# zx_kit_example.net
KiCad netlist of a schematic drawn in EAGLE
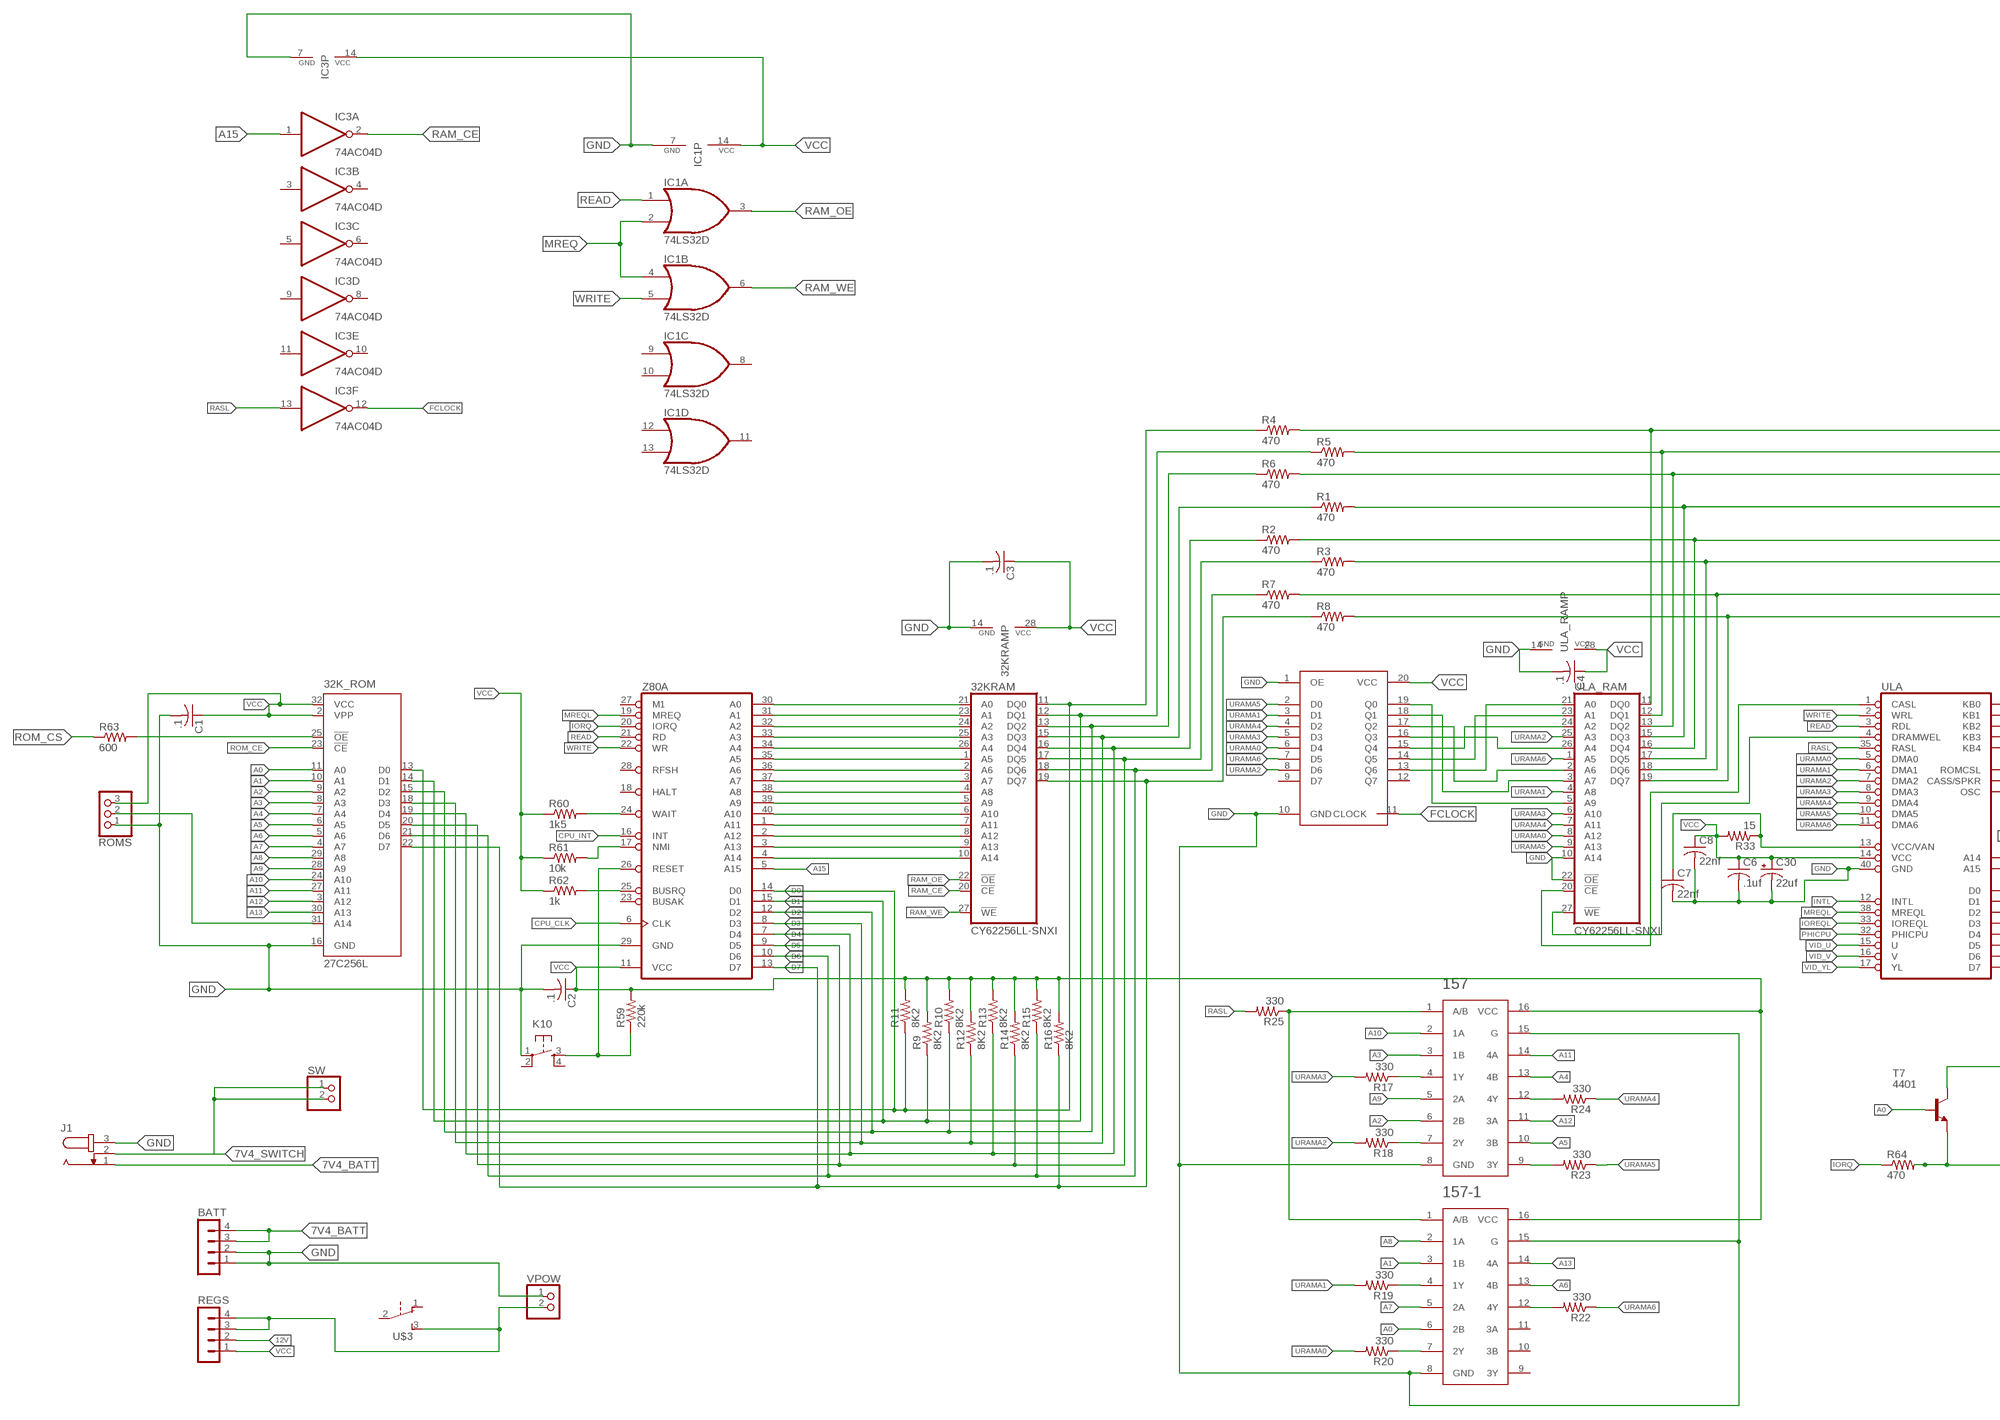
[diagram p0: schematic, sheet 1, part 1 of 3]
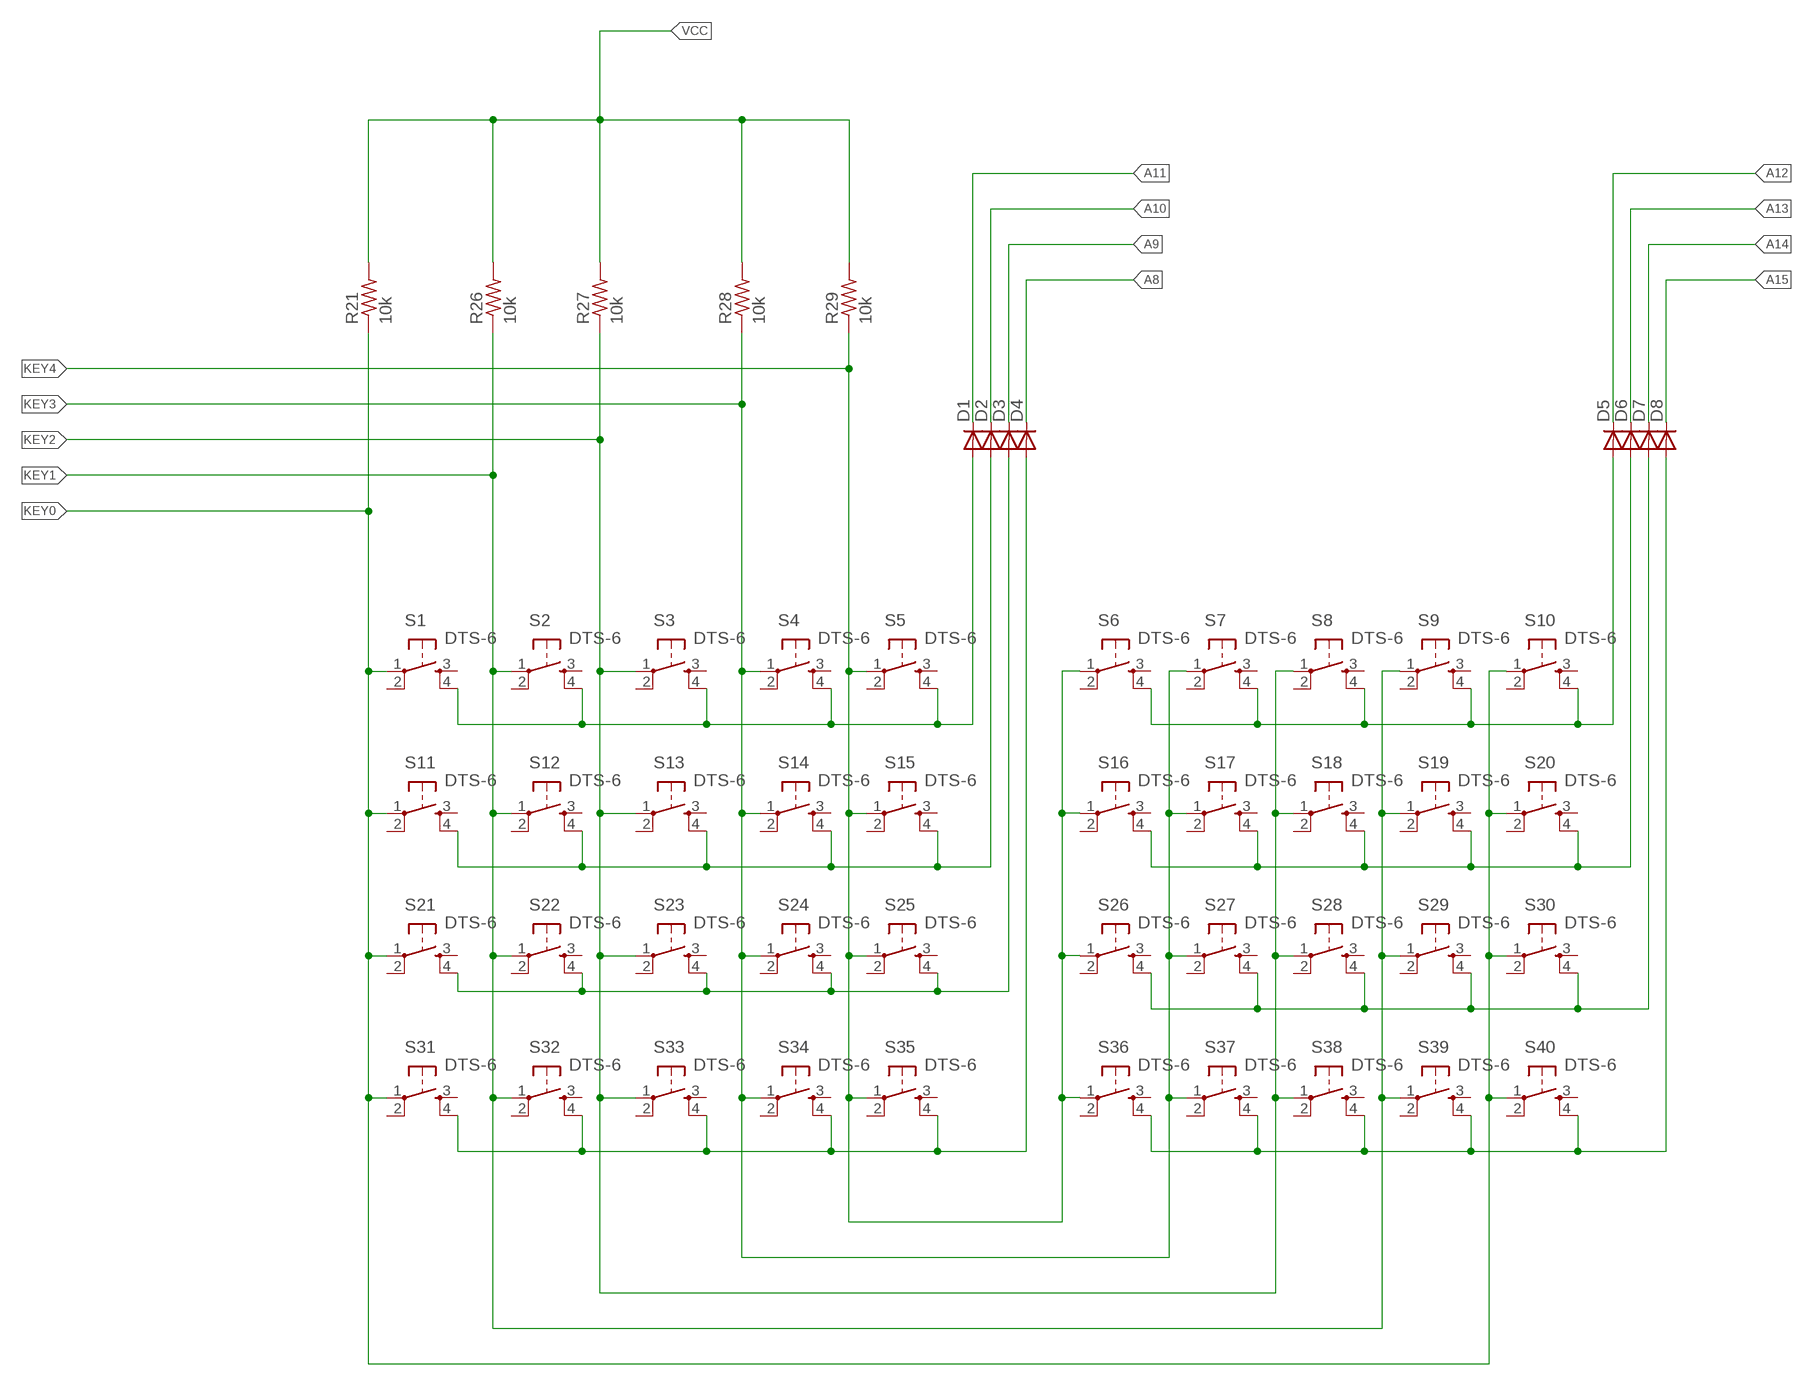
[diagram p1: schematic, sheet 1, part 2 of 3]
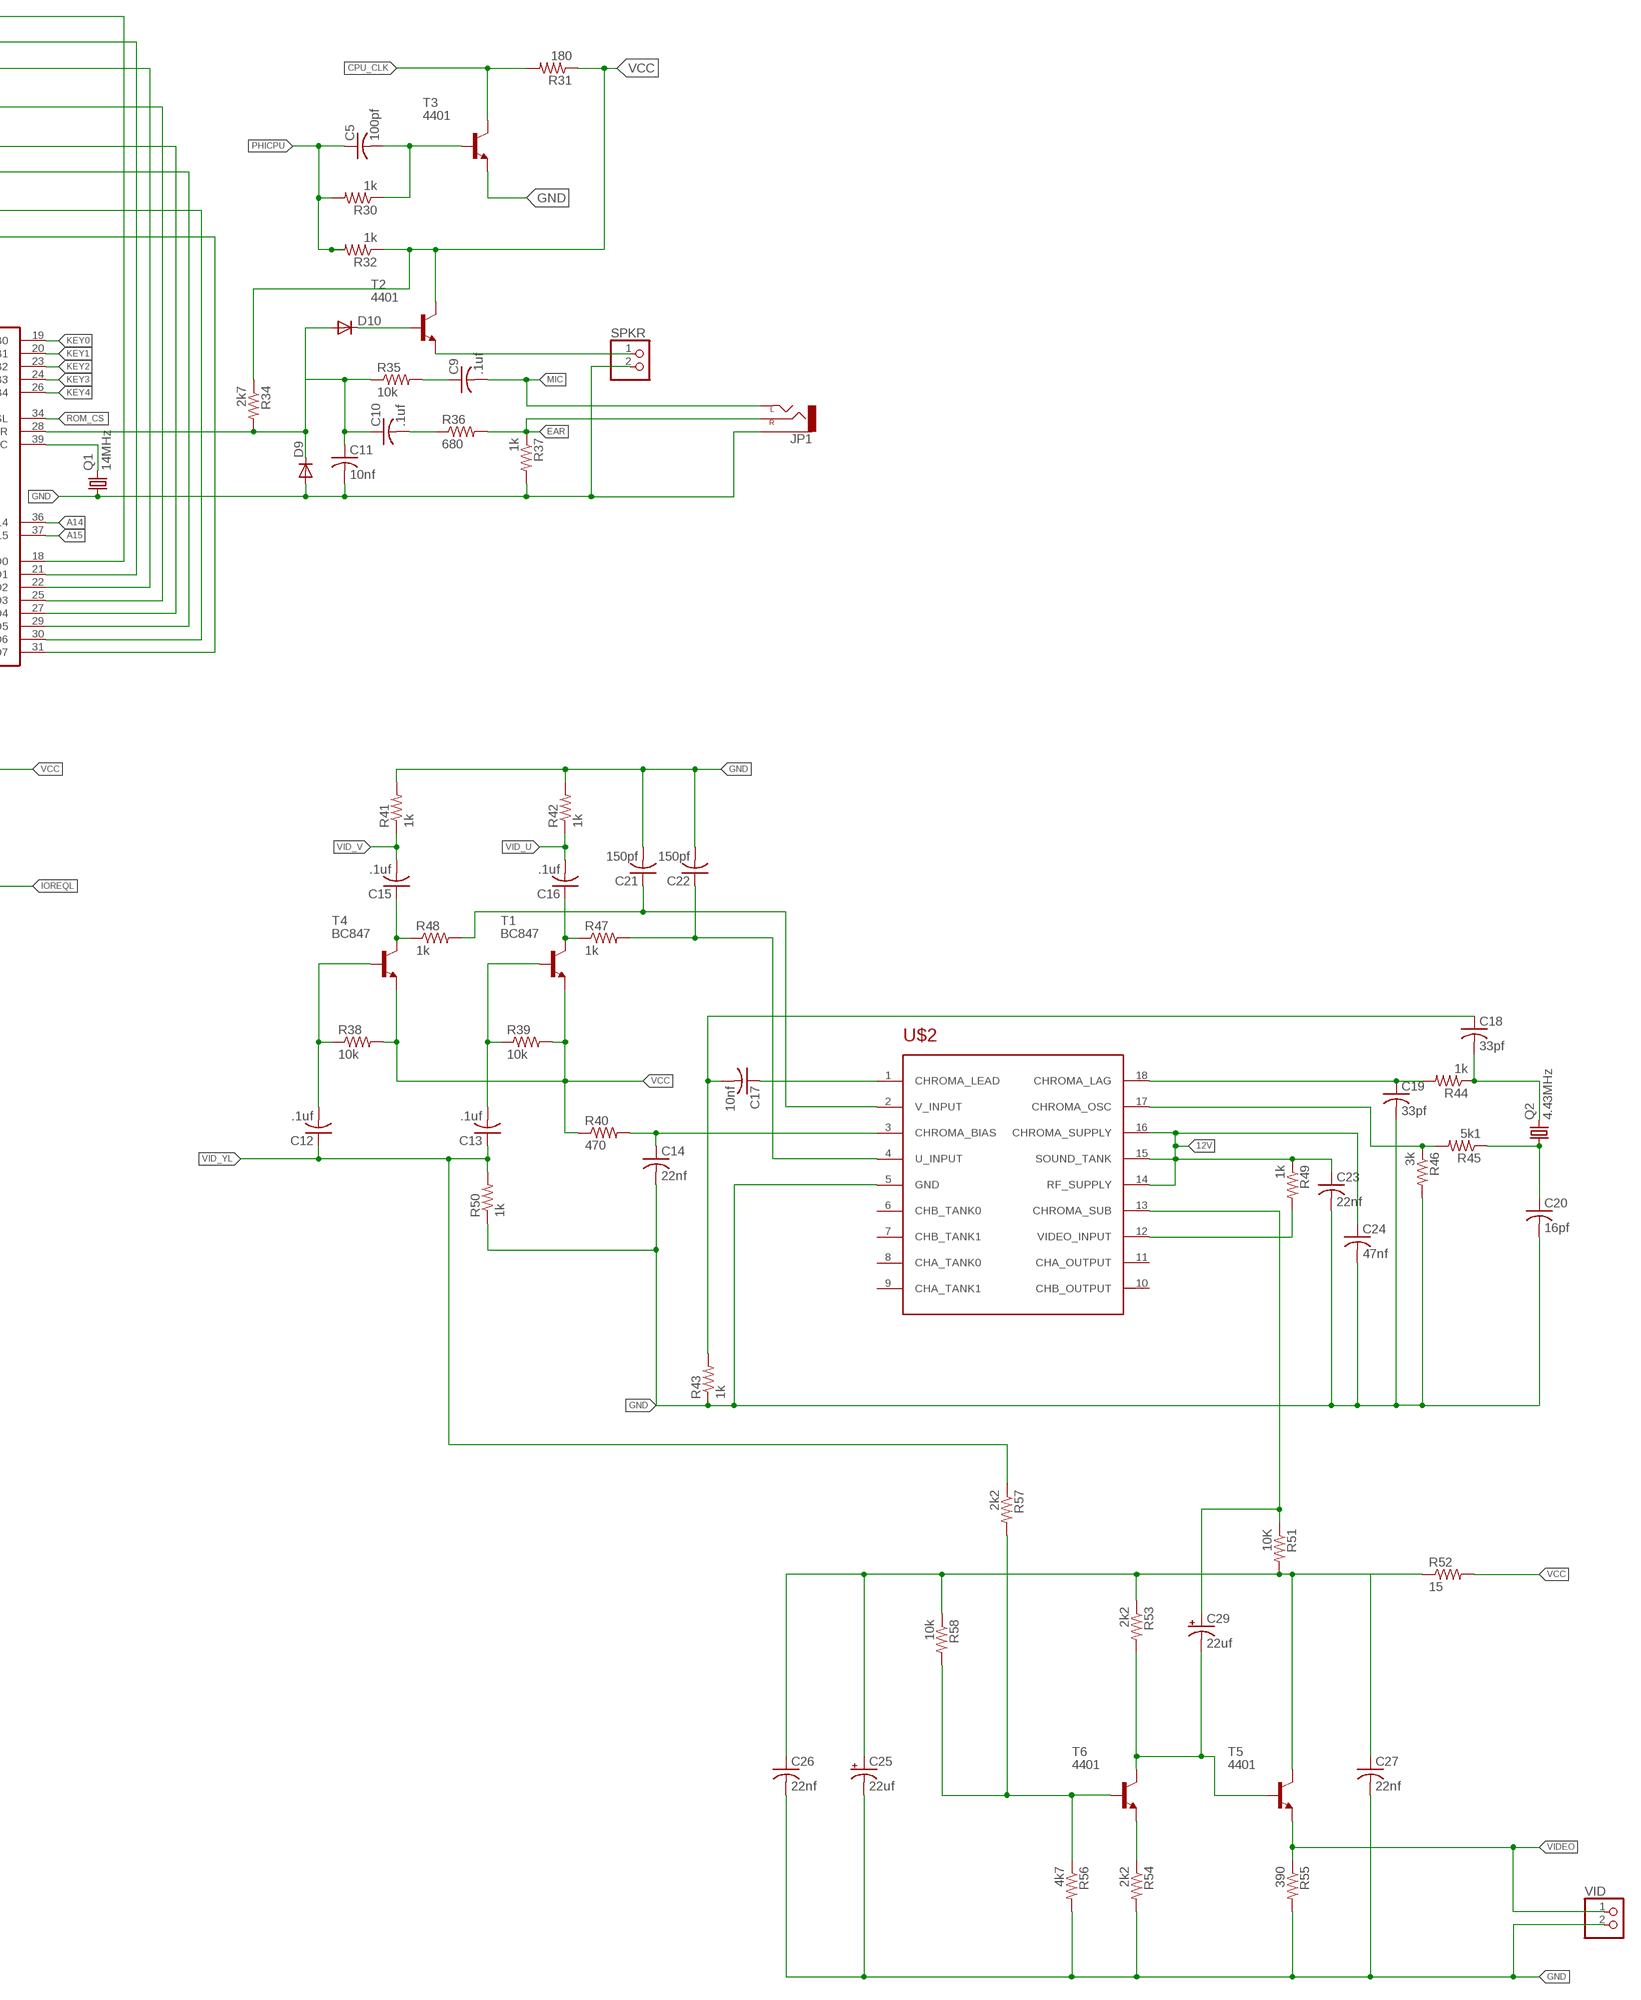
[diagram p2: schematic, sheet 1, part 3 of 3]

(export (version "E")
  (design (tool "Eeschema 10.0.6"))
  (components
    (comp (ref "32KRAM")
      (value "CY62256LL-SNXI")
      (footprint "eagle-import:SOJ28_3")
      (libsource (lib "eagle-import") (part "CY62256LL-?SNXI"))
    )
    (comp (ref "32K_ROM")
      (value "27C256L")
      (footprint "eagle-import:PLCC-32")
      (fields (field (name "MPN") "AT27C256R-70JU"))
      (libsource (lib "eagle-import") (part "27256LC"))
    )
    (comp (ref "157")
      (value "SN74HC157D")
      (footprint "eagle-import:SO16")
      (libsource (lib "eagle-import") (part "SN74HC157D"))
    )
    (comp (ref "157-1")
      (value "SN74HC157D")
      (footprint "eagle-import:SO16")
      (libsource (lib "eagle-import") (part "SN74HC157D"))
    )
    (comp (ref "BATT")
      (value "MA04-1")
      (footprint "eagle-import:MA04-1")
      (libsource (lib "eagle-import") (part "MA04-1"))
    )
    (comp (ref "C1")
      (value ".1")
      (footprint "eagle-import:C0805")
      (libsource (lib "eagle-import") (part "resistor_C-USC0805"))
    )
    (comp (ref "C2")
      (value ".1")
      (footprint "eagle-import:C0805")
      (libsource (lib "eagle-import") (part "resistor_C-USC0805"))
    )
    (comp (ref "C3")
      (value ".1")
      (footprint "eagle-import:C0805")
      (libsource (lib "eagle-import") (part "resistor_C-USC0805"))
    )
    (comp (ref "C4")
      (value ".1")
      (footprint "eagle-import:C0805")
      (libsource (lib "eagle-import") (part "resistor_C-USC0805"))
    )
    (comp (ref "C5")
      (value "100pf")
      (footprint "eagle-import:C0805")
      (libsource (lib "eagle-import") (part "C-USC0805"))
    )
    (comp (ref "C6")
      (value ".1uf")
      (footprint "eagle-import:C0805")
      (libsource (lib "eagle-import") (part "C-USC0805"))
    )
    (comp (ref "C7")
      (value "22nf")
      (footprint "eagle-import:C0805")
      (libsource (lib "eagle-import") (part "C-USC0805"))
    )
    (comp (ref "C8")
      (value "22nf")
      (footprint "eagle-import:C0805")
      (libsource (lib "eagle-import") (part "C-USC0805"))
    )
    (comp (ref "C9")
      (value ".1uf")
      (footprint "eagle-import:C0805")
      (libsource (lib "eagle-import") (part "C-USC0805"))
    )
    (comp (ref "C10")
      (value ".1uf")
      (footprint "eagle-import:C0805")
      (libsource (lib "eagle-import") (part "C-USC0805"))
    )
    (comp (ref "C11")
      (value "10nf")
      (footprint "eagle-import:C0805")
      (libsource (lib "eagle-import") (part "C-USC0805"))
    )
    (comp (ref "C12")
      (value ".1uf")
      (footprint "eagle-import:C0805")
      (libsource (lib "eagle-import") (part "C-USC0805"))
    )
    (comp (ref "C13")
      (value ".1uf")
      (footprint "eagle-import:C0805")
      (libsource (lib "eagle-import") (part "C-USC0805"))
    )
    (comp (ref "C14")
      (value "22nf")
      (footprint "eagle-import:C0805")
      (libsource (lib "eagle-import") (part "C-USC0805"))
    )
    (comp (ref "C15")
      (value ".1uf")
      (footprint "eagle-import:C0805")
      (libsource (lib "eagle-import") (part "C-USC0805"))
    )
    (comp (ref "C16")
      (value ".1uf")
      (footprint "eagle-import:C0805")
      (libsource (lib "eagle-import") (part "C-USC0805"))
    )
    (comp (ref "C17")
      (value "10nf")
      (footprint "eagle-import:C0805")
      (libsource (lib "eagle-import") (part "C-USC0805"))
    )
    (comp (ref "C18")
      (value "33pf")
      (footprint "eagle-import:C0805")
      (libsource (lib "eagle-import") (part "C-USC0805"))
    )
    (comp (ref "C19")
      (value "33pf")
      (footprint "eagle-import:C0805")
      (libsource (lib "eagle-import") (part "C-USC0805"))
    )
    (comp (ref "C20")
      (value "16pf")
      (footprint "eagle-import:C0805")
      (libsource (lib "eagle-import") (part "C-USC0805"))
    )
    (comp (ref "C21")
      (value "150pf")
      (footprint "eagle-import:C0805")
      (libsource (lib "eagle-import") (part "C-USC0805"))
    )
    (comp (ref "C22")
      (value "150pf")
      (footprint "eagle-import:C0805")
      (libsource (lib "eagle-import") (part "C-USC0805"))
    )
    (comp (ref "C23")
      (value "22nf")
      (footprint "eagle-import:C0805")
      (libsource (lib "eagle-import") (part "C-USC0805"))
    )
    (comp (ref "C24")
      (value "47nf")
      (footprint "eagle-import:C0805")
      (libsource (lib "eagle-import") (part "C-USC0805"))
    )
    (comp (ref "C25")
      (value "22uf")
      (footprint "eagle-import:PANASONIC_B")
      (libsource (lib "eagle-import") (part "CPOL-USB"))
    )
    (comp (ref "C26")
      (value "22nf")
      (footprint "eagle-import:C0805")
      (libsource (lib "eagle-import") (part "C-USC0805"))
    )
    (comp (ref "C27")
      (value "22nf")
      (footprint "eagle-import:C0805")
      (libsource (lib "eagle-import") (part "C-USC0805"))
    )
    (comp (ref "C29")
      (value "22uf")
      (footprint "eagle-import:PANASONIC_B")
      (libsource (lib "eagle-import") (part "CPOL-USB"))
    )
    (comp (ref "C30")
      (value "22uf")
      (footprint "eagle-import:PANASONIC_B")
      (libsource (lib "eagle-import") (part "CPOL-USB"))
    )
    (comp (ref "D1")
      (value "DIODE-SOD123")
      (footprint "eagle-import:SOD123")
      (libsource (lib "eagle-import") (part "DIODE-SOD123"))
    )
    (comp (ref "D2")
      (value "DIODE-SOD123")
      (footprint "eagle-import:SOD123")
      (libsource (lib "eagle-import") (part "DIODE-SOD123"))
    )
    (comp (ref "D3")
      (value "DIODE-SOD123")
      (footprint "eagle-import:SOD123")
      (libsource (lib "eagle-import") (part "DIODE-SOD123"))
    )
    (comp (ref "D4")
      (value "DIODE-SOD123")
      (footprint "eagle-import:SOD123")
      (libsource (lib "eagle-import") (part "DIODE-SOD123"))
    )
    (comp (ref "D5")
      (value "DIODE-SOD123")
      (footprint "eagle-import:SOD123")
      (libsource (lib "eagle-import") (part "DIODE-SOD123"))
    )
    (comp (ref "D6")
      (value "DIODE-SOD123")
      (footprint "eagle-import:SOD123")
      (libsource (lib "eagle-import") (part "DIODE-SOD123"))
    )
    (comp (ref "D7")
      (value "DIODE-SOD123")
      (footprint "eagle-import:SOD123")
      (libsource (lib "eagle-import") (part "DIODE-SOD123"))
    )
    (comp (ref "D8")
      (value "DIODE-SOD123")
      (footprint "eagle-import:SOD123")
      (libsource (lib "eagle-import") (part "DIODE-SOD123"))
    )
    (comp (ref "D9")
      (value "DIODE-SOD123")
      (footprint "eagle-import:SOD123")
      (libsource (lib "eagle-import") (part "DIODE-SOD123"))
    )
    (comp (ref "D10")
      (value "DIODE-SOD123")
      (footprint "eagle-import:SOD123")
      (libsource (lib "eagle-import") (part "DIODE-SOD123"))
    )
    (comp (ref "IC1")
      (value "74LS32D")
      (footprint "eagle-import:SO14")
      (libsource (lib "eagle-import") (part "7432DLS"))
    )
    (comp (ref "IC3")
      (value "74AC04D")
      (footprint "eagle-import:SO14")
      (libsource (lib "eagle-import") (part "7404DAC"))
    )
    (comp (ref "J1")
      (value "JACK-PLUG0")
      (footprint "eagle-import:SPC4077")
      (libsource (lib "eagle-import") (part "JACK-PLUG0"))
    )
    (comp (ref "JP1")
      (value "AUDIO-JACKPTH")
      (footprint "eagle-import:AUDIO-JACK")
      (libsource (lib "eagle-import") (part "AUDIO-JACKPTH"))
    )
    (comp (ref "K10")
      (value "DTS-6")
      (footprint "eagle-import:DTS-6")
      (libsource (lib "eagle-import") (part "DTS-6"))
    )
    (comp (ref "Q1")
      (value "14MHz")
      (footprint "eagle-import:CTS406")
      (libsource (lib "eagle-import") (part "CRYSTALCTS406"))
    )
    (comp (ref "Q2")
      (value "4.43MHz")
      (footprint "eagle-import:HC49_S")
      (libsource (lib "eagle-import") (part "CRYSTALHC49S"))
    )
    (comp (ref "R1")
      (value "470")
      (footprint "eagle-import:M0805")
      (libsource (lib "eagle-import") (part "R-US_M0805"))
    )
    (comp (ref "R2")
      (value "470")
      (footprint "eagle-import:M0805")
      (libsource (lib "eagle-import") (part "R-US_M0805"))
    )
    (comp (ref "R3")
      (value "470")
      (footprint "eagle-import:M0805")
      (libsource (lib "eagle-import") (part "R-US_M0805"))
    )
    (comp (ref "R4")
      (value "470")
      (footprint "eagle-import:M0805")
      (libsource (lib "eagle-import") (part "R-US_M0805"))
    )
    (comp (ref "R5")
      (value "470")
      (footprint "eagle-import:M0805")
      (libsource (lib "eagle-import") (part "R-US_M0805"))
    )
    (comp (ref "R6")
      (value "470")
      (footprint "eagle-import:M0805")
      (libsource (lib "eagle-import") (part "R-US_M0805"))
    )
    (comp (ref "R7")
      (value "470")
      (footprint "eagle-import:M0805")
      (libsource (lib "eagle-import") (part "R-US_M0805"))
    )
    (comp (ref "R8")
      (value "470")
      (footprint "eagle-import:M0805")
      (libsource (lib "eagle-import") (part "R-US_M0805"))
    )
    (comp (ref "R9")
      (value "8K2")
      (footprint "eagle-import:M0805")
      (libsource (lib "eagle-import") (part "R-US_M0805"))
    )
    (comp (ref "R10")
      (value "8K2")
      (footprint "eagle-import:M0805")
      (libsource (lib "eagle-import") (part "R-US_M0805"))
    )
    (comp (ref "R11")
      (value "8K2")
      (footprint "eagle-import:M0805")
      (libsource (lib "eagle-import") (part "R-US_M0805"))
    )
    (comp (ref "R12")
      (value "8K2")
      (footprint "eagle-import:M0805")
      (libsource (lib "eagle-import") (part "R-US_M0805"))
    )
    (comp (ref "R13")
      (value "8K2")
      (footprint "eagle-import:M0805")
      (libsource (lib "eagle-import") (part "R-US_M0805"))
    )
    (comp (ref "R14")
      (value "8K2")
      (footprint "eagle-import:M0805")
      (libsource (lib "eagle-import") (part "R-US_M0805"))
    )
    (comp (ref "R15")
      (value "8K2")
      (footprint "eagle-import:M0805")
      (libsource (lib "eagle-import") (part "R-US_M0805"))
    )
    (comp (ref "R16")
      (value "8K2")
      (footprint "eagle-import:M0805")
      (libsource (lib "eagle-import") (part "R-US_M0805"))
    )
    (comp (ref "R17")
      (value "330")
      (footprint "eagle-import:M0805")
      (libsource (lib "eagle-import") (part "R-US_M0805"))
    )
    (comp (ref "R18")
      (value "330")
      (footprint "eagle-import:M0805")
      (libsource (lib "eagle-import") (part "R-US_M0805"))
    )
    (comp (ref "R19")
      (value "330")
      (footprint "eagle-import:M0805")
      (libsource (lib "eagle-import") (part "R-US_M0805"))
    )
    (comp (ref "R20")
      (value "330")
      (footprint "eagle-import:M0805")
      (libsource (lib "eagle-import") (part "R-US_M0805"))
    )
    (comp (ref "R21")
      (value "10k")
      (footprint "eagle-import:R0805")
      (libsource (lib "eagle-import") (part "R-US_R0805"))
    )
    (comp (ref "R22")
      (value "330")
      (footprint "eagle-import:M0805")
      (libsource (lib "eagle-import") (part "R-US_M0805"))
    )
    (comp (ref "R23")
      (value "330")
      (footprint "eagle-import:M0805")
      (libsource (lib "eagle-import") (part "R-US_M0805"))
    )
    (comp (ref "R24")
      (value "330")
      (footprint "eagle-import:M0805")
      (libsource (lib "eagle-import") (part "R-US_M0805"))
    )
    (comp (ref "R25")
      (value "330")
      (footprint "eagle-import:M0805")
      (libsource (lib "eagle-import") (part "R-US_M0805"))
    )
    (comp (ref "R26")
      (value "10k")
      (footprint "eagle-import:R0805")
      (libsource (lib "eagle-import") (part "R-US_R0805"))
    )
    (comp (ref "R27")
      (value "10k")
      (footprint "eagle-import:R0805")
      (libsource (lib "eagle-import") (part "R-US_R0805"))
    )
    (comp (ref "R28")
      (value "10k")
      (footprint "eagle-import:R0805")
      (libsource (lib "eagle-import") (part "R-US_R0805"))
    )
    (comp (ref "R29")
      (value "10k")
      (footprint "eagle-import:R0805")
      (libsource (lib "eagle-import") (part "R-US_R0805"))
    )
    (comp (ref "R30")
      (value "1k")
      (footprint "eagle-import:R0805")
      (libsource (lib "eagle-import") (part "R-US_R0805"))
    )
    (comp (ref "R31")
      (value "180")
      (footprint "eagle-import:R0805")
      (libsource (lib "eagle-import") (part "R-US_R0805"))
    )
    (comp (ref "R32")
      (value "1k")
      (footprint "eagle-import:R0805")
      (libsource (lib "eagle-import") (part "R-US_R0805"))
    )
    (comp (ref "R33")
      (value "15")
      (footprint "eagle-import:R0805")
      (libsource (lib "eagle-import") (part "R-US_R0805"))
    )
    (comp (ref "R34")
      (value "2k7")
      (footprint "eagle-import:R0805")
      (libsource (lib "eagle-import") (part "R-US_R0805"))
    )
    (comp (ref "R35")
      (value "10k")
      (footprint "eagle-import:R0805")
      (libsource (lib "eagle-import") (part "R-US_R0805"))
    )
    (comp (ref "R36")
      (value "680")
      (footprint "eagle-import:R0805")
      (libsource (lib "eagle-import") (part "R-US_R0805"))
    )
    (comp (ref "R37")
      (value "1k")
      (footprint "eagle-import:R0805")
      (libsource (lib "eagle-import") (part "R-US_R0805"))
    )
    (comp (ref "R38")
      (value "10k")
      (footprint "eagle-import:R0805")
      (libsource (lib "eagle-import") (part "R-US_R0805"))
    )
    (comp (ref "R39")
      (value "10k")
      (footprint "eagle-import:R0805")
      (libsource (lib "eagle-import") (part "R-US_R0805"))
    )
    (comp (ref "R40")
      (value "470")
      (footprint "eagle-import:R0805")
      (libsource (lib "eagle-import") (part "R-US_R0805"))
    )
    (comp (ref "R41")
      (value "1k")
      (footprint "eagle-import:R0805")
      (libsource (lib "eagle-import") (part "R-US_R0805"))
    )
    (comp (ref "R42")
      (value "1k")
      (footprint "eagle-import:R0805")
      (libsource (lib "eagle-import") (part "R-US_R0805"))
    )
    (comp (ref "R43")
      (value "1k")
      (footprint "eagle-import:R0805")
      (libsource (lib "eagle-import") (part "R-US_R0805"))
    )
    (comp (ref "R44")
      (value "1k")
      (footprint "eagle-import:R0805")
      (libsource (lib "eagle-import") (part "R-US_R0805"))
    )
    (comp (ref "R45")
      (value "5k1")
      (footprint "eagle-import:R0805")
      (libsource (lib "eagle-import") (part "R-US_R0805"))
    )
    (comp (ref "R46")
      (value "3k")
      (footprint "eagle-import:R0805")
      (libsource (lib "eagle-import") (part "R-US_R0805"))
    )
    (comp (ref "R47")
      (value "1k")
      (footprint "eagle-import:R0805")
      (libsource (lib "eagle-import") (part "R-US_R0805"))
    )
    (comp (ref "R48")
      (value "1k")
      (footprint "eagle-import:R0805")
      (libsource (lib "eagle-import") (part "R-US_R0805"))
    )
    (comp (ref "R49")
      (value "1k")
      (footprint "eagle-import:R0805")
      (libsource (lib "eagle-import") (part "R-US_R0805"))
    )
    (comp (ref "R50")
      (value "1k")
      (footprint "eagle-import:R0805")
      (libsource (lib "eagle-import") (part "R-US_R0805"))
    )
    (comp (ref "R51")
      (value "10K")
      (footprint "eagle-import:R0805")
      (libsource (lib "eagle-import") (part "R-US_R0805"))
    )
    (comp (ref "R52")
      (value "15")
      (footprint "eagle-import:R0805")
      (libsource (lib "eagle-import") (part "R-US_R0805"))
    )
    (comp (ref "R53")
      (value "2k2")
      (footprint "eagle-import:R0805")
      (libsource (lib "eagle-import") (part "R-US_R0805"))
    )
    (comp (ref "R54")
      (value "2k2")
      (footprint "eagle-import:R0805")
      (libsource (lib "eagle-import") (part "R-US_R0805"))
    )
    (comp (ref "R55")
      (value "390")
      (footprint "eagle-import:R0805")
      (libsource (lib "eagle-import") (part "R-US_R0805"))
    )
    (comp (ref "R56")
      (value "4k7")
      (footprint "eagle-import:R0805")
      (libsource (lib "eagle-import") (part "R-US_R0805"))
    )
    (comp (ref "R57")
      (value "2k2")
      (footprint "eagle-import:R0805")
      (libsource (lib "eagle-import") (part "R-US_R0805"))
    )
    (comp (ref "R58")
      (value "10k")
      (footprint "eagle-import:R0805")
      (libsource (lib "eagle-import") (part "R-US_R0805"))
    )
    (comp (ref "R59")
      (value "220k")
      (footprint "eagle-import:M0805")
      (libsource (lib "eagle-import") (part "R-US_M0805"))
    )
    (comp (ref "R60")
      (value "1k5")
      (footprint "eagle-import:M0805")
      (libsource (lib "eagle-import") (part "R-US_M0805"))
    )
    (comp (ref "R61")
      (value "10k")
      (footprint "eagle-import:M0805")
      (libsource (lib "eagle-import") (part "R-US_M0805"))
    )
    (comp (ref "R62")
      (value "1k")
      (footprint "eagle-import:M0805")
      (libsource (lib "eagle-import") (part "R-US_M0805"))
    )
    (comp (ref "R63")
      (value "600")
      (footprint "eagle-import:M0805")
      (libsource (lib "eagle-import") (part "R-US_M0805"))
    )
    (comp (ref "R64")
      (value "470")
      (footprint "eagle-import:R0805")
      (libsource (lib "eagle-import") (part "R-US_R0805"))
    )
    (comp (ref "REGS")
      (value "MA04-1")
      (footprint "eagle-import:MA04-1")
      (libsource (lib "eagle-import") (part "MA04-1"))
    )
    (comp (ref "ROMS")
      (value "PINHD-1X3")
      (footprint "eagle-import:1X03")
      (libsource (lib "eagle-import") (part "PINHD-1X3"))
    )
    (comp (ref "S1")
      (value "DTS-6")
      (footprint "eagle-import:DTS-6")
      (libsource (lib "eagle-import") (part "DTS-6"))
    )
    (comp (ref "S2")
      (value "DTS-6")
      (footprint "eagle-import:DTS-6")
      (libsource (lib "eagle-import") (part "DTS-6"))
    )
    (comp (ref "S3")
      (value "DTS-6")
      (footprint "eagle-import:DTS-6")
      (libsource (lib "eagle-import") (part "DTS-6"))
    )
    (comp (ref "S4")
      (value "DTS-6")
      (footprint "eagle-import:DTS-6")
      (libsource (lib "eagle-import") (part "DTS-6"))
    )
    (comp (ref "S5")
      (value "DTS-6")
      (footprint "eagle-import:DTS-6")
      (libsource (lib "eagle-import") (part "DTS-6"))
    )
    (comp (ref "S6")
      (value "DTS-6")
      (footprint "eagle-import:DTS-6")
      (libsource (lib "eagle-import") (part "DTS-6"))
    )
    (comp (ref "S7")
      (value "DTS-6")
      (footprint "eagle-import:DTS-6")
      (libsource (lib "eagle-import") (part "DTS-6"))
    )
    (comp (ref "S8")
      (value "DTS-6")
      (footprint "eagle-import:DTS-6")
      (libsource (lib "eagle-import") (part "DTS-6"))
    )
    (comp (ref "S9")
      (value "DTS-6")
      (footprint "eagle-import:DTS-6")
      (libsource (lib "eagle-import") (part "DTS-6"))
    )
    (comp (ref "S10")
      (value "DTS-6")
      (footprint "eagle-import:DTS-6")
      (libsource (lib "eagle-import") (part "DTS-6"))
    )
    (comp (ref "S11")
      (value "DTS-6")
      (footprint "eagle-import:DTS-6")
      (libsource (lib "eagle-import") (part "DTS-6"))
    )
    (comp (ref "S12")
      (value "DTS-6")
      (footprint "eagle-import:DTS-6")
      (libsource (lib "eagle-import") (part "DTS-6"))
    )
    (comp (ref "S13")
      (value "DTS-6")
      (footprint "eagle-import:DTS-6")
      (libsource (lib "eagle-import") (part "DTS-6"))
    )
    (comp (ref "S14")
      (value "DTS-6")
      (footprint "eagle-import:DTS-6")
      (libsource (lib "eagle-import") (part "DTS-6"))
    )
    (comp (ref "S15")
      (value "DTS-6")
      (footprint "eagle-import:DTS-6")
      (libsource (lib "eagle-import") (part "DTS-6"))
    )
    (comp (ref "S16")
      (value "DTS-6")
      (footprint "eagle-import:DTS-6")
      (libsource (lib "eagle-import") (part "DTS-6"))
    )
    (comp (ref "S17")
      (value "DTS-6")
      (footprint "eagle-import:DTS-6")
      (libsource (lib "eagle-import") (part "DTS-6"))
    )
    (comp (ref "S18")
      (value "DTS-6")
      (footprint "eagle-import:DTS-6")
      (libsource (lib "eagle-import") (part "DTS-6"))
    )
    (comp (ref "S19")
      (value "DTS-6")
      (footprint "eagle-import:DTS-6")
      (libsource (lib "eagle-import") (part "DTS-6"))
    )
    (comp (ref "S20")
      (value "DTS-6")
      (footprint "eagle-import:DTS-6")
      (libsource (lib "eagle-import") (part "DTS-6"))
    )
    (comp (ref "S21")
      (value "DTS-6")
      (footprint "eagle-import:DTS-6")
      (libsource (lib "eagle-import") (part "DTS-6"))
    )
    (comp (ref "S22")
      (value "DTS-6")
      (footprint "eagle-import:DTS-6")
      (libsource (lib "eagle-import") (part "DTS-6"))
    )
    (comp (ref "S23")
      (value "DTS-6")
      (footprint "eagle-import:DTS-6")
      (libsource (lib "eagle-import") (part "DTS-6"))
    )
    (comp (ref "S24")
      (value "DTS-6")
      (footprint "eagle-import:DTS-6")
      (libsource (lib "eagle-import") (part "DTS-6"))
    )
    (comp (ref "S25")
      (value "DTS-6")
      (footprint "eagle-import:DTS-6")
      (libsource (lib "eagle-import") (part "DTS-6"))
    )
    (comp (ref "S26")
      (value "DTS-6")
      (footprint "eagle-import:DTS-6")
      (libsource (lib "eagle-import") (part "DTS-6"))
    )
    (comp (ref "S27")
      (value "DTS-6")
      (footprint "eagle-import:DTS-6")
      (libsource (lib "eagle-import") (part "DTS-6"))
    )
    (comp (ref "S28")
      (value "DTS-6")
      (footprint "eagle-import:DTS-6")
      (libsource (lib "eagle-import") (part "DTS-6"))
    )
    (comp (ref "S29")
      (value "DTS-6")
      (footprint "eagle-import:DTS-6")
      (libsource (lib "eagle-import") (part "DTS-6"))
    )
    (comp (ref "S30")
      (value "DTS-6")
      (footprint "eagle-import:DTS-6")
      (libsource (lib "eagle-import") (part "DTS-6"))
    )
    (comp (ref "S31")
      (value "DTS-6")
      (footprint "eagle-import:DTS-6")
      (libsource (lib "eagle-import") (part "DTS-6"))
    )
    (comp (ref "S32")
      (value "DTS-6")
      (footprint "eagle-import:DTS-6")
      (libsource (lib "eagle-import") (part "DTS-6"))
    )
    (comp (ref "S33")
      (value "DTS-6")
      (footprint "eagle-import:DTS-6")
      (libsource (lib "eagle-import") (part "DTS-6"))
    )
    (comp (ref "S34")
      (value "DTS-6")
      (footprint "eagle-import:DTS-6")
      (libsource (lib "eagle-import") (part "DTS-6"))
    )
    (comp (ref "S35")
      (value "DTS-6")
      (footprint "eagle-import:DTS-6")
      (libsource (lib "eagle-import") (part "DTS-6"))
    )
    (comp (ref "S36")
      (value "DTS-6")
      (footprint "eagle-import:DTS-6")
      (libsource (lib "eagle-import") (part "DTS-6"))
    )
    (comp (ref "S37")
      (value "DTS-6")
      (footprint "eagle-import:DTS-6")
      (libsource (lib "eagle-import") (part "DTS-6"))
    )
    (comp (ref "S38")
      (value "DTS-6")
      (footprint "eagle-import:DTS-6")
      (libsource (lib "eagle-import") (part "DTS-6"))
    )
    (comp (ref "S39")
      (value "DTS-6")
      (footprint "eagle-import:DTS-6")
      (libsource (lib "eagle-import") (part "DTS-6"))
    )
    (comp (ref "S40")
      (value "DTS-6")
      (footprint "eagle-import:DTS-6")
      (libsource (lib "eagle-import") (part "DTS-6"))
    )
    (comp (ref "SPKR")
      (value "PINHD-1X2")
      (footprint "eagle-import:1X02")
      (libsource (lib "eagle-import") (part "PINHD-1X2"))
    )
    (comp (ref "SW")
      (value "PINHD-1X2")
      (footprint "eagle-import:1X02")
      (libsource (lib "eagle-import") (part "PINHD-1X2"))
    )
    (comp (ref "T1")
      (value "BC847")
      (footprint "eagle-import:SOT23")
      (libsource (lib "eagle-import") (part "BC847"))
    )
    (comp (ref "T2")
      (value "4401")
      (footprint "eagle-import:SOT23-BEC")
      (libsource (lib "eagle-import") (part "-NPN-SOT23-BECMMBT4401LT1"))
    )
    (comp (ref "T3")
      (value "4401")
      (footprint "eagle-import:SOT23-BEC")
      (libsource (lib "eagle-import") (part "-NPN-SOT23-BECMMBT4401LT1"))
    )
    (comp (ref "T4")
      (value "BC847")
      (footprint "eagle-import:SOT23")
      (libsource (lib "eagle-import") (part "BC847"))
    )
    (comp (ref "T5")
      (value "4401")
      (footprint "eagle-import:SOT23-BEC")
      (libsource (lib "eagle-import") (part "-NPN-SOT23-BECMMBT4401LT1"))
    )
    (comp (ref "T6")
      (value "4401")
      (footprint "eagle-import:SOT23-BEC")
      (libsource (lib "eagle-import") (part "-NPN-SOT23-BECMMBT4401LT1"))
    )
    (comp (ref "T7")
      (value "4401")
      (footprint "eagle-import:SOT23-BEC")
      (libsource (lib "eagle-import") (part "-NPN-SOT23-BECMMBT4401LT1"))
    )
    (comp (ref "U$1")
      (value "MC74HC574A")
      (footprint "eagle-import:SO20W")
      (libsource (lib "eagle-import") (part "MC74HC574A"))
    )
    (comp (ref "U$2")
      (value "LM1889")
      (footprint "eagle-import:SOCKET-18")
      (libsource (lib "eagle-import") (part "LM1889"))
    )
    (comp (ref "U$3")
      (value "MS12ASW30_01")
      (footprint "eagle-import:MS12ASG30_01")
      (libsource (lib "eagle-import") (part "MS12ASW30_01"))
    )
    (comp (ref "ULA")
      (value "ZXULA")
      (footprint "eagle-import:DIL40")
      (libsource (lib "eagle-import") (part "ZXULA"))
    )
    (comp (ref "ULA_RAM")
      (value "CY62256LL-SNXI")
      (footprint "eagle-import:SOJ28_3")
      (libsource (lib "eagle-import") (part "CY62256LL-?SNXI"))
    )
    (comp (ref "VID")
      (value "PINHD-1X2")
      (footprint "eagle-import:1X02")
      (libsource (lib "eagle-import") (part "PINHD-1X2"))
    )
    (comp (ref "VPOW")
      (value "PINHD-1X2")
      (footprint "eagle-import:1X02")
      (libsource (lib "eagle-import") (part "PINHD-1X2"))
    )
    (comp (ref "Z80A")
      (value "Z80CPU")
      (footprint "eagle-import:DIL40")
      (libsource (lib "eagle-import") (part "Z80CPU"))
    )
  )
  (nets
    (net (code "1") (name "7V4_BATT") (class "Default")
      (node (ref "BATT") (pin "3") (pinfunction "3_3") (pintype "passive"))
      (node (ref "BATT") (pin "4") (pinfunction "4_4") (pintype "passive"))
      (node (ref "J1") (pin "1") (pinfunction "1_1") (pintype "passive"))
    )
    (net (code "2") (name "7V4_SWITCH") (class "Default")
      (node (ref "J1") (pin "2") (pinfunction "2_2") (pintype "passive"))
      (node (ref "SW") (pin "1") (pinfunction "1_1") (pintype "passive"))
      (node (ref "SW") (pin "2") (pinfunction "2_2") (pintype "passive"))
    )
    (net (code "3") (name "12V") (class "Default")
      (node (ref "C23") (pin "1") (pinfunction "1_1") (pintype "passive"))
      (node (ref "C24") (pin "1") (pinfunction "1_1") (pintype "passive"))
      (node (ref "R49") (pin "1") (pinfunction "1_1") (pintype "passive"))
      (node (ref "REGS") (pin "2") (pinfunction "2_2") (pintype "passive"))
      (node (ref "U$2") (pin "14") (pinfunction "RF_SUPPLY_14") (pintype "bidirectional"))
      (node (ref "U$2") (pin "15") (pinfunction "SOUND_TANK_15") (pintype "bidirectional"))
      (node (ref "U$2") (pin "16") (pinfunction "CHROMA_SUPPLY_16") (pintype "bidirectional"))
    )
    (net (code "4") (name "A0") (class "Default")
      (node (ref "157-1") (pin "6") (pinfunction "2B_6") (pintype "bidirectional"))
      (node (ref "32KRAM") (pin "21") (pinfunction "A0_21") (pintype "input"))
      (node (ref "32K_ROM") (pin "11") (pinfunction "A0_11") (pintype "input"))
      (node (ref "T7") (pin "B") (pinfunction "B_B") (pintype "passive"))
      (node (ref "Z80A") (pin "30") (pinfunction "A0_30") (pintype "output"))
    )
    (net (code "5") (name "A1") (class "Default")
      (node (ref "157-1") (pin "3") (pinfunction "1B_3") (pintype "bidirectional"))
      (node (ref "32KRAM") (pin "23") (pinfunction "A1_23") (pintype "input"))
      (node (ref "32K_ROM") (pin "10") (pinfunction "A1_10") (pintype "input"))
      (node (ref "Z80A") (pin "31") (pinfunction "A1_31") (pintype "output"))
    )
    (net (code "6") (name "A2") (class "Default")
      (node (ref "157") (pin "6") (pinfunction "2B_6") (pintype "bidirectional"))
      (node (ref "32KRAM") (pin "24") (pinfunction "A2_24") (pintype "input"))
      (node (ref "32K_ROM") (pin "9") (pinfunction "A2_9") (pintype "input"))
      (node (ref "Z80A") (pin "32") (pinfunction "A2_32") (pintype "output"))
    )
    (net (code "7") (name "A3") (class "Default")
      (node (ref "157") (pin "3") (pinfunction "1B_3") (pintype "bidirectional"))
      (node (ref "32KRAM") (pin "25") (pinfunction "A3_25") (pintype "input"))
      (node (ref "32K_ROM") (pin "8") (pinfunction "A3_8") (pintype "input"))
      (node (ref "Z80A") (pin "33") (pinfunction "A3_33") (pintype "output"))
    )
    (net (code "8") (name "A4") (class "Default")
      (node (ref "157") (pin "13") (pinfunction "4B_13") (pintype "bidirectional"))
      (node (ref "32KRAM") (pin "26") (pinfunction "A4_26") (pintype "input"))
      (node (ref "32K_ROM") (pin "7") (pinfunction "A4_7") (pintype "input"))
      (node (ref "Z80A") (pin "34") (pinfunction "A4_34") (pintype "output"))
    )
    (net (code "9") (name "A5") (class "Default")
      (node (ref "157") (pin "10") (pinfunction "3B_10") (pintype "bidirectional"))
      (node (ref "32KRAM") (pin "1") (pinfunction "A5_1") (pintype "input"))
      (node (ref "32K_ROM") (pin "6") (pinfunction "A5_6") (pintype "input"))
      (node (ref "Z80A") (pin "35") (pinfunction "A5_35") (pintype "output"))
    )
    (net (code "10") (name "A6") (class "Default")
      (node (ref "157-1") (pin "13") (pinfunction "4B_13") (pintype "bidirectional"))
      (node (ref "32KRAM") (pin "2") (pinfunction "A6_2") (pintype "input"))
      (node (ref "32K_ROM") (pin "5") (pinfunction "A6_5") (pintype "input"))
      (node (ref "Z80A") (pin "36") (pinfunction "A6_36") (pintype "output"))
    )
    (net (code "11") (name "A7") (class "Default")
      (node (ref "157-1") (pin "5") (pinfunction "2A_5") (pintype "bidirectional"))
      (node (ref "32KRAM") (pin "3") (pinfunction "A7_3") (pintype "input"))
      (node (ref "32K_ROM") (pin "4") (pinfunction "A7_4") (pintype "input"))
      (node (ref "Z80A") (pin "37") (pinfunction "A7_37") (pintype "output"))
    )
    (net (code "12") (name "A8") (class "Default")
      (node (ref "157-1") (pin "2") (pinfunction "1A_2") (pintype "bidirectional"))
      (node (ref "32KRAM") (pin "4") (pinfunction "A8_4") (pintype "input"))
      (node (ref "32K_ROM") (pin "29") (pinfunction "A8_29") (pintype "input"))
      (node (ref "D4") (pin "C") (pinfunction "C_C") (pintype "passive"))
      (node (ref "Z80A") (pin "38") (pinfunction "A8_38") (pintype "output"))
    )
    (net (code "13") (name "A9") (class "Default")
      (node (ref "157") (pin "5") (pinfunction "2A_5") (pintype "bidirectional"))
      (node (ref "32KRAM") (pin "5") (pinfunction "A9_5") (pintype "input"))
      (node (ref "32K_ROM") (pin "28") (pinfunction "A9_28") (pintype "input"))
      (node (ref "D3") (pin "C") (pinfunction "C_C") (pintype "passive"))
      (node (ref "Z80A") (pin "39") (pinfunction "A9_39") (pintype "output"))
    )
    (net (code "14") (name "A10") (class "Default")
      (node (ref "157") (pin "2") (pinfunction "1A_2") (pintype "bidirectional"))
      (node (ref "32KRAM") (pin "6") (pinfunction "A10_6") (pintype "input"))
      (node (ref "32K_ROM") (pin "24") (pinfunction "A10_24") (pintype "input"))
      (node (ref "D2") (pin "C") (pinfunction "C_C") (pintype "passive"))
      (node (ref "Z80A") (pin "40") (pinfunction "A10_40") (pintype "output"))
    )
    (net (code "15") (name "A11") (class "Default")
      (node (ref "157") (pin "14") (pinfunction "4A_14") (pintype "bidirectional"))
      (node (ref "32KRAM") (pin "7") (pinfunction "A11_7") (pintype "input"))
      (node (ref "32K_ROM") (pin "27") (pinfunction "A11_27") (pintype "input"))
      (node (ref "D1") (pin "C") (pinfunction "C_C") (pintype "passive"))
      (node (ref "Z80A") (pin "1") (pinfunction "A11_1") (pintype "output"))
    )
    (net (code "16") (name "A12") (class "Default")
      (node (ref "157") (pin "11") (pinfunction "3A_11") (pintype "bidirectional"))
      (node (ref "32KRAM") (pin "8") (pinfunction "A12_8") (pintype "input"))
      (node (ref "32K_ROM") (pin "3") (pinfunction "A12_3") (pintype "input"))
      (node (ref "D5") (pin "C") (pinfunction "C_C") (pintype "passive"))
      (node (ref "Z80A") (pin "2") (pinfunction "A12_2") (pintype "output"))
    )
    (net (code "17") (name "A13") (class "Default")
      (node (ref "157-1") (pin "14") (pinfunction "4A_14") (pintype "bidirectional"))
      (node (ref "32KRAM") (pin "9") (pinfunction "A13_9") (pintype "input"))
      (node (ref "32K_ROM") (pin "30") (pinfunction "A13_30") (pintype "input"))
      (node (ref "D6") (pin "C") (pinfunction "C_C") (pintype "passive"))
      (node (ref "Z80A") (pin "3") (pinfunction "A13_3") (pintype "output"))
    )
    (net (code "18") (name "A14") (class "Default")
      (node (ref "32KRAM") (pin "10") (pinfunction "A14_10") (pintype "input"))
      (node (ref "D7") (pin "C") (pinfunction "C_C") (pintype "passive"))
      (node (ref "ULA") (pin "36") (pinfunction "A14_36") (pintype "output"))
      (node (ref "Z80A") (pin "4") (pinfunction "A14_4") (pintype "output"))
    )
    (net (code "19") (name "A15") (class "Default")
      (node (ref "D8") (pin "C") (pinfunction "C_C") (pintype "passive"))
      (node (ref "IC3") (pin "1") (pinfunction "I_1") (pintype "input"))
      (node (ref "ULA") (pin "37") (pinfunction "A15_37") (pintype "output"))
      (node (ref "Z80A") (pin "5") (pinfunction "A15_5") (pintype "output"))
    )
    (net (code "20") (name "CPU_CLK") (class "Default")
      (node (ref "R31") (pin "2") (pinfunction "2_2") (pintype "passive"))
      (node (ref "T3") (pin "C") (pinfunction "C_C") (pintype "passive"))
      (node (ref "Z80A") (pin "6") (pinfunction "CLK_6") (pintype "input"))
    )
    (net (code "21") (name "CPU_INT") (class "Default")
      (node (ref "Z80A") (pin "16") (pinfunction "INT_16") (pintype "input"))
    )
    (net (code "22") (name "D0") (class "Default")
      (node (ref "32KRAM") (pin "11") (pinfunction "DQ0_11") (pintype "bidirectional"))
      (node (ref "32K_ROM") (pin "13") (pinfunction "D0_13") (pintype "tri_state"))
      (node (ref "R11") (pin "1") (pinfunction "1_1") (pintype "passive"))
      (node (ref "R4") (pin "1") (pinfunction "1_1") (pintype "passive"))
      (node (ref "Z80A") (pin "14") (pinfunction "D0_14") (pintype "bidirectional"))
    )
    (net (code "23") (name "D1") (class "Default")
      (node (ref "32KRAM") (pin "12") (pinfunction "DQ1_12") (pintype "bidirectional"))
      (node (ref "32K_ROM") (pin "14") (pinfunction "D1_14") (pintype "tri_state"))
      (node (ref "R5") (pin "1") (pinfunction "1_1") (pintype "passive"))
      (node (ref "R9") (pin "1") (pinfunction "1_1") (pintype "passive"))
      (node (ref "Z80A") (pin "15") (pinfunction "D1_15") (pintype "bidirectional"))
    )
    (net (code "24") (name "D2") (class "Default")
      (node (ref "32KRAM") (pin "13") (pinfunction "DQ2_13") (pintype "bidirectional"))
      (node (ref "32K_ROM") (pin "15") (pinfunction "D2_15") (pintype "tri_state"))
      (node (ref "R10") (pin "1") (pinfunction "1_1") (pintype "passive"))
      (node (ref "R6") (pin "1") (pinfunction "1_1") (pintype "passive"))
      (node (ref "Z80A") (pin "12") (pinfunction "D2_12") (pintype "bidirectional"))
    )
    (net (code "25") (name "D3") (class "Default")
      (node (ref "32KRAM") (pin "15") (pinfunction "DQ3_15") (pintype "bidirectional"))
      (node (ref "32K_ROM") (pin "18") (pinfunction "D3_18") (pintype "tri_state"))
      (node (ref "R1") (pin "1") (pinfunction "1_1") (pintype "passive"))
      (node (ref "R12") (pin "1") (pinfunction "1_1") (pintype "passive"))
      (node (ref "Z80A") (pin "8") (pinfunction "D3_8") (pintype "bidirectional"))
    )
    (net (code "26") (name "D4") (class "Default")
      (node (ref "32KRAM") (pin "16") (pinfunction "DQ4_16") (pintype "bidirectional"))
      (node (ref "32K_ROM") (pin "19") (pinfunction "D4_19") (pintype "tri_state"))
      (node (ref "R13") (pin "1") (pinfunction "1_1") (pintype "passive"))
      (node (ref "R2") (pin "1") (pinfunction "1_1") (pintype "passive"))
      (node (ref "Z80A") (pin "7") (pinfunction "D4_7") (pintype "bidirectional"))
    )
    (net (code "27") (name "D5") (class "Default")
      (node (ref "32KRAM") (pin "17") (pinfunction "DQ5_17") (pintype "bidirectional"))
      (node (ref "32K_ROM") (pin "20") (pinfunction "D5_20") (pintype "tri_state"))
      (node (ref "R14") (pin "1") (pinfunction "1_1") (pintype "passive"))
      (node (ref "R3") (pin "1") (pinfunction "1_1") (pintype "passive"))
      (node (ref "Z80A") (pin "9") (pinfunction "D5_9") (pintype "bidirectional"))
    )
    (net (code "28") (name "D6") (class "Default")
      (node (ref "32KRAM") (pin "18") (pinfunction "DQ6_18") (pintype "bidirectional"))
      (node (ref "32K_ROM") (pin "21") (pinfunction "D6_21") (pintype "tri_state"))
      (node (ref "R15") (pin "1") (pinfunction "1_1") (pintype "passive"))
      (node (ref "R7") (pin "1") (pinfunction "1_1") (pintype "passive"))
      (node (ref "Z80A") (pin "10") (pinfunction "D6_10") (pintype "bidirectional"))
    )
    (net (code "29") (name "D7") (class "Default")
      (node (ref "32KRAM") (pin "19") (pinfunction "DQ7_19") (pintype "bidirectional"))
      (node (ref "32K_ROM") (pin "22") (pinfunction "D7_22") (pintype "tri_state"))
      (node (ref "R16") (pin "1") (pinfunction "1_1") (pintype "passive"))
      (node (ref "R8") (pin "1") (pinfunction "1_1") (pintype "passive"))
      (node (ref "Z80A") (pin "13") (pinfunction "D7_13") (pintype "bidirectional"))
    )
    (net (code "30") (name "EAR") (class "Default")
      (node (ref "JP1") (pin "RING") (pinfunction "RIGHT_RING") (pintype "bidirectional"))
      (node (ref "R36") (pin "2") (pinfunction "2_2") (pintype "passive"))
      (node (ref "R37") (pin "1") (pinfunction "1_1") (pintype "passive"))
    )
    (net (code "31") (name "FCLOCK") (class "Default")
      (node (ref "IC3") (pin "12") (pinfunction "O_12") (pintype "output"))
      (node (ref "U$1") (pin "11") (pinfunction "CLOCK_11") (pintype "bidirectional"))
    )
    (net (code "32") (name "GND") (class "Default")
      (node (ref "157") (pin "15") (pinfunction "G_15") (pintype "bidirectional"))
      (node (ref "157") (pin "8") (pinfunction "GND_8") (pintype "bidirectional"))
      (node (ref "157-1") (pin "15") (pinfunction "G_15") (pintype "bidirectional"))
      (node (ref "157-1") (pin "8") (pinfunction "GND_8") (pintype "bidirectional"))
      (node (ref "32KRAM") (pin "14") (pinfunction "GND_14") (pintype "power_in"))
      (node (ref "32K_ROM") (pin "16") (pinfunction "GND_16") (pintype "power_in"))
      (node (ref "BATT") (pin "1") (pinfunction "1_1") (pintype "passive"))
      (node (ref "BATT") (pin "2") (pinfunction "2_2") (pintype "passive"))
      (node (ref "C1") (pin "2") (pinfunction "2_2") (pintype "passive"))
      (node (ref "C11") (pin "2") (pinfunction "2_2") (pintype "passive"))
      (node (ref "C14") (pin "2") (pinfunction "2_2") (pintype "passive"))
      (node (ref "C19") (pin "2") (pinfunction "2_2") (pintype "passive"))
      (node (ref "C2") (pin "2") (pinfunction "2_2") (pintype "passive"))
      (node (ref "C20") (pin "2") (pinfunction "2_2") (pintype "passive"))
      (node (ref "C21") (pin "2") (pinfunction "2_2") (pintype "passive"))
      (node (ref "C22") (pin "2") (pinfunction "2_2") (pintype "passive"))
      (node (ref "C23") (pin "2") (pinfunction "2_2") (pintype "passive"))
      (node (ref "C24") (pin "2") (pinfunction "2_2") (pintype "passive"))
      (node (ref "C25") (pin "-") (pinfunction "-_-") (pintype "passive"))
      (node (ref "C26") (pin "2") (pinfunction "2_2") (pintype "passive"))
      (node (ref "C27") (pin "2") (pinfunction "2_2") (pintype "passive"))
      (node (ref "C3") (pin "2") (pinfunction "2_2") (pintype "passive"))
      (node (ref "C30") (pin "-") (pinfunction "-_-") (pintype "passive"))
      (node (ref "C4") (pin "2") (pinfunction "2_2") (pintype "passive"))
      (node (ref "C6") (pin "2") (pinfunction "2_2") (pintype "passive"))
      (node (ref "C7") (pin "2") (pinfunction "2_2") (pintype "passive"))
      (node (ref "C8") (pin "2") (pinfunction "2_2") (pintype "passive"))
      (node (ref "D9") (pin "A") (pinfunction "A_A") (pintype "passive"))
      (node (ref "IC1") (pin "7") (pinfunction "GND_7") (pintype "power_in"))
      (node (ref "IC3") (pin "7") (pinfunction "GND_7") (pintype "power_in"))
      (node (ref "J1") (pin "3") (pinfunction "3_3") (pintype "passive"))
      (node (ref "JP1") (pin "SLEEVE") (pinfunction "SLEEVE_SLEEVE") (pintype "bidirectional"))
      (node (ref "K10") (pin "1") (pinfunction "1_1") (pintype "passive"))
      (node (ref "Q1") (pin "1") (pinfunction "1_1") (pintype "passive"))
      (node (ref "R37") (pin "2") (pinfunction "2_2") (pintype "passive"))
      (node (ref "R41") (pin "2") (pinfunction "2_2") (pintype "passive"))
      (node (ref "R42") (pin "2") (pinfunction "2_2") (pintype "passive"))
      (node (ref "R43") (pin "1") (pinfunction "1_1") (pintype "passive"))
      (node (ref "R46") (pin "2") (pinfunction "2_2") (pintype "passive"))
      (node (ref "R50") (pin "1") (pinfunction "1_1") (pintype "passive"))
      (node (ref "R54") (pin "2") (pinfunction "2_2") (pintype "passive"))
      (node (ref "R55") (pin "2") (pinfunction "2_2") (pintype "passive"))
      (node (ref "R56") (pin "2") (pinfunction "2_2") (pintype "passive"))
      (node (ref "ROMS") (pin "1") (pinfunction "1_1") (pintype "passive"))
      (node (ref "SPKR") (pin "2") (pinfunction "2_2") (pintype "passive"))
      (node (ref "T3") (pin "E") (pinfunction "E_E") (pintype "passive"))
      (node (ref "U$1") (pin "1") (pinfunction "OE_1") (pintype "bidirectional"))
      (node (ref "U$1") (pin "10") (pinfunction "GND_10") (pintype "bidirectional"))
      (node (ref "U$2") (pin "5") (pinfunction "GND_5") (pintype "bidirectional"))
      (node (ref "ULA") (pin "40") (pinfunction "GND_40") (pintype "output"))
      (node (ref "ULA_RAM") (pin "10") (pinfunction "A14_10") (pintype "input"))
      (node (ref "ULA_RAM") (pin "14") (pinfunction "GND_14") (pintype "power_in"))
      (node (ref "ULA_RAM") (pin "22") (pinfunction "~{OE}_22") (pintype "input"))
      (node (ref "VID") (pin "2") (pinfunction "2_2") (pintype "passive"))
      (node (ref "VPOW") (pin "1") (pinfunction "1_1") (pintype "passive"))
      (node (ref "Z80A") (pin "29") (pinfunction "GND_29") (pintype "power_in"))
    )
    (net (code "33") (name "INTL") (class "Default")
      (node (ref "ULA") (pin "12") (pinfunction "INTL_12") (pintype "input"))
    )
    (net (code "34") (name "IOREQL") (class "Default")
      (node (ref "R64") (pin "2") (pinfunction "2_2") (pintype "passive"))
      (node (ref "T7") (pin "E") (pinfunction "E_E") (pintype "passive"))
      (node (ref "ULA") (pin "33") (pinfunction "IOREQL_33") (pintype "output"))
    )
    (net (code "35") (name "IORQ") (class "Default")
      (node (ref "R64") (pin "1") (pinfunction "1_1") (pintype "passive"))
      (node (ref "Z80A") (pin "20") (pinfunction "IORQ_20") (pintype "output"))
    )
    (net (code "36") (name "KEY0") (class "Default")
      (node (ref "R21") (pin "1") (pinfunction "1_1") (pintype "passive"))
      (node (ref "S1") (pin "1") (pinfunction "1_1") (pintype "passive"))
      (node (ref "S10") (pin "1") (pinfunction "1_1") (pintype "passive"))
      (node (ref "S11") (pin "1") (pinfunction "1_1") (pintype "passive"))
      (node (ref "S20") (pin "1") (pinfunction "1_1") (pintype "passive"))
      (node (ref "S21") (pin "1") (pinfunction "1_1") (pintype "passive"))
      (node (ref "S30") (pin "1") (pinfunction "1_1") (pintype "passive"))
      (node (ref "S31") (pin "1") (pinfunction "1_1") (pintype "passive"))
      (node (ref "S40") (pin "1") (pinfunction "1_1") (pintype "passive"))
      (node (ref "ULA") (pin "19") (pinfunction "KB0_19") (pintype "output"))
    )
    (net (code "37") (name "KEY1") (class "Default")
      (node (ref "R26") (pin "1") (pinfunction "1_1") (pintype "passive"))
      (node (ref "S12") (pin "1") (pinfunction "1_1") (pintype "passive"))
      (node (ref "S19") (pin "1") (pinfunction "1_1") (pintype "passive"))
      (node (ref "S2") (pin "1") (pinfunction "1_1") (pintype "passive"))
      (node (ref "S22") (pin "1") (pinfunction "1_1") (pintype "passive"))
      (node (ref "S29") (pin "1") (pinfunction "1_1") (pintype "passive"))
      (node (ref "S32") (pin "1") (pinfunction "1_1") (pintype "passive"))
      (node (ref "S39") (pin "1") (pinfunction "1_1") (pintype "passive"))
      (node (ref "S9") (pin "1") (pinfunction "1_1") (pintype "passive"))
      (node (ref "ULA") (pin "20") (pinfunction "KB1_20") (pintype "output"))
    )
    (net (code "38") (name "KEY2") (class "Default")
      (node (ref "R27") (pin "1") (pinfunction "1_1") (pintype "passive"))
      (node (ref "S13") (pin "1") (pinfunction "1_1") (pintype "passive"))
      (node (ref "S18") (pin "1") (pinfunction "1_1") (pintype "passive"))
      (node (ref "S23") (pin "1") (pinfunction "1_1") (pintype "passive"))
      (node (ref "S28") (pin "1") (pinfunction "1_1") (pintype "passive"))
      (node (ref "S3") (pin "1") (pinfunction "1_1") (pintype "passive"))
      (node (ref "S33") (pin "1") (pinfunction "1_1") (pintype "passive"))
      (node (ref "S38") (pin "1") (pinfunction "1_1") (pintype "passive"))
      (node (ref "S8") (pin "1") (pinfunction "1_1") (pintype "passive"))
      (node (ref "ULA") (pin "23") (pinfunction "KB2_23") (pintype "output"))
    )
    (net (code "39") (name "KEY3") (class "Default")
      (node (ref "R28") (pin "1") (pinfunction "1_1") (pintype "passive"))
      (node (ref "S14") (pin "1") (pinfunction "1_1") (pintype "passive"))
      (node (ref "S17") (pin "1") (pinfunction "1_1") (pintype "passive"))
      (node (ref "S24") (pin "1") (pinfunction "1_1") (pintype "passive"))
      (node (ref "S27") (pin "1") (pinfunction "1_1") (pintype "passive"))
      (node (ref "S34") (pin "1") (pinfunction "1_1") (pintype "passive"))
      (node (ref "S37") (pin "1") (pinfunction "1_1") (pintype "passive"))
      (node (ref "S4") (pin "1") (pinfunction "1_1") (pintype "passive"))
      (node (ref "S7") (pin "1") (pinfunction "1_1") (pintype "passive"))
      (node (ref "ULA") (pin "24") (pinfunction "KB3_24") (pintype "output"))
    )
    (net (code "40") (name "KEY4") (class "Default")
      (node (ref "R29") (pin "1") (pinfunction "1_1") (pintype "passive"))
      (node (ref "S15") (pin "1") (pinfunction "1_1") (pintype "passive"))
      (node (ref "S16") (pin "1") (pinfunction "1_1") (pintype "passive"))
      (node (ref "S25") (pin "1") (pinfunction "1_1") (pintype "passive"))
      (node (ref "S26") (pin "1") (pinfunction "1_1") (pintype "passive"))
      (node (ref "S35") (pin "1") (pinfunction "1_1") (pintype "passive"))
      (node (ref "S36") (pin "1") (pinfunction "1_1") (pintype "passive"))
      (node (ref "S5") (pin "1") (pinfunction "1_1") (pintype "passive"))
      (node (ref "S6") (pin "1") (pinfunction "1_1") (pintype "passive"))
      (node (ref "ULA") (pin "26") (pinfunction "KB4_26") (pintype "output"))
    )
    (net (code "41") (name "MIC") (class "Default")
      (node (ref "C9") (pin "2") (pinfunction "2_2") (pintype "passive"))
      (node (ref "JP1") (pin "TIP") (pinfunction "LEFT_TIP") (pintype "bidirectional"))
    )
    (net (code "42") (name "MREQ") (class "Default")
      (node (ref "IC1") (pin "2") (pinfunction "I1_2") (pintype "input"))
      (node (ref "IC1") (pin "4") (pinfunction "I0_4") (pintype "input"))
    )
    (net (code "43") (name "MREQL") (class "Default")
      (node (ref "ULA") (pin "38") (pinfunction "MREQL_38") (pintype "output"))
      (node (ref "Z80A") (pin "19") (pinfunction "MREQ_19") (pintype "output"))
    )
    (net (code "44") (name "Net-(32K_ROM-A14)") (class "Default")
      (node (ref "32K_ROM") (pin "31") (pinfunction "A14_31") (pintype "input"))
      (node (ref "ROMS") (pin "2") (pinfunction "2_2") (pintype "passive"))
    )
    (net (code "45") (name "Net-(32K_ROM-~{OE})") (class "Default")
      (node (ref "32K_ROM") (pin "25") (pinfunction "~{OE}_25") (pintype "input"))
      (node (ref "R63") (pin "2") (pinfunction "2_2") (pintype "passive"))
    )
    (net (code "46") (name "Net-(157-1-1Y)") (class "Default")
      (node (ref "157-1") (pin "4") (pinfunction "1Y_4") (pintype "bidirectional"))
      (node (ref "R19") (pin "1") (pinfunction "1_1") (pintype "passive"))
    )
    (net (code "47") (name "Net-(157-1-2Y)") (class "Default")
      (node (ref "157-1") (pin "7") (pinfunction "2Y_7") (pintype "bidirectional"))
      (node (ref "R20") (pin "1") (pinfunction "1_1") (pintype "passive"))
    )
    (net (code "48") (name "Net-(157-1-4Y)") (class "Default")
      (node (ref "157-1") (pin "12") (pinfunction "4Y_12") (pintype "bidirectional"))
      (node (ref "R22") (pin "2") (pinfunction "2_2") (pintype "passive"))
    )
    (net (code "49") (name "Net-(157-1-A{slash}B)") (class "Default")
      (node (ref "157") (pin "1") (pinfunction "A/B_1") (pintype "bidirectional"))
      (node (ref "157-1") (pin "1") (pinfunction "A/B_1") (pintype "bidirectional"))
      (node (ref "R25") (pin "1") (pinfunction "1_1") (pintype "passive"))
    )
    (net (code "50") (name "Net-(157-1Y)") (class "Default")
      (node (ref "157") (pin "4") (pinfunction "1Y_4") (pintype "bidirectional"))
      (node (ref "R17") (pin "1") (pinfunction "1_1") (pintype "passive"))
    )
    (net (code "51") (name "Net-(157-2Y)") (class "Default")
      (node (ref "157") (pin "7") (pinfunction "2Y_7") (pintype "bidirectional"))
      (node (ref "R18") (pin "1") (pinfunction "1_1") (pintype "passive"))
    )
    (net (code "52") (name "Net-(157-3Y)") (class "Default")
      (node (ref "157") (pin "9") (pinfunction "3Y_9") (pintype "bidirectional"))
      (node (ref "R23") (pin "2") (pinfunction "2_2") (pintype "passive"))
    )
    (net (code "53") (name "Net-(157-4Y)") (class "Default")
      (node (ref "157") (pin "12") (pinfunction "4Y_12") (pintype "bidirectional"))
      (node (ref "R24") (pin "2") (pinfunction "2_2") (pintype "passive"))
    )
    (net (code "54") (name "Net-(C5-Pad2)") (class "Default")
      (node (ref "C5") (pin "2") (pinfunction "2_2") (pintype "passive"))
      (node (ref "R30") (pin "1") (pinfunction "1_1") (pintype "passive"))
      (node (ref "T3") (pin "B") (pinfunction "B_B") (pintype "passive"))
    )
    (net (code "55") (name "Net-(C9-Pad1)") (class "Default")
      (node (ref "C9") (pin "1") (pinfunction "1_1") (pintype "passive"))
      (node (ref "R35") (pin "2") (pinfunction "2_2") (pintype "passive"))
    )
    (net (code "56") (name "Net-(C10-Pad2)") (class "Default")
      (node (ref "C10") (pin "2") (pinfunction "2_2") (pintype "passive"))
      (node (ref "R36") (pin "1") (pinfunction "1_1") (pintype "passive"))
    )
    (net (code "57") (name "Net-(C17-Pad2)") (class "Default")
      (node (ref "C17") (pin "2") (pinfunction "2_2") (pintype "passive"))
      (node (ref "C18") (pin "1") (pinfunction "1_1") (pintype "passive"))
      (node (ref "R43") (pin "2") (pinfunction "2_2") (pintype "passive"))
    )
    (net (code "58") (name "Net-(C18-Pad2)") (class "Default")
      (node (ref "C18") (pin "2") (pinfunction "2_2") (pintype "passive"))
      (node (ref "Q2") (pin "2") (pinfunction "2_2") (pintype "passive"))
      (node (ref "R44") (pin "1") (pinfunction "1_1") (pintype "passive"))
    )
    (net (code "59") (name "Net-(C20-Pad1)") (class "Default")
      (node (ref "C20") (pin "1") (pinfunction "1_1") (pintype "passive"))
      (node (ref "Q2") (pin "1") (pinfunction "1_1") (pintype "passive"))
      (node (ref "R45") (pin "1") (pinfunction "1_1") (pintype "passive"))
    )
    (net (code "60") (name "Net-(C25-Pad+)") (class "Default")
      (node (ref "C25") (pin "+") (pinfunction "+_+") (pintype "passive"))
      (node (ref "C26") (pin "1") (pinfunction "1_1") (pintype "passive"))
      (node (ref "C27") (pin "1") (pinfunction "1_1") (pintype "passive"))
      (node (ref "R51") (pin "2") (pinfunction "2_2") (pintype "passive"))
      (node (ref "R52") (pin "1") (pinfunction "1_1") (pintype "passive"))
      (node (ref "R53") (pin "1") (pinfunction "1_1") (pintype "passive"))
      (node (ref "R58") (pin "1") (pinfunction "1_1") (pintype "passive"))
      (node (ref "T5") (pin "C") (pinfunction "C_C") (pintype "passive"))
    )
    (net (code "61") (name "Net-(C29-Pad-)") (class "Default")
      (node (ref "C29") (pin "-") (pinfunction "-_-") (pintype "passive"))
      (node (ref "R53") (pin "2") (pinfunction "2_2") (pintype "passive"))
      (node (ref "T5") (pin "B") (pinfunction "B_B") (pintype "passive"))
      (node (ref "T6") (pin "C") (pinfunction "C_C") (pintype "passive"))
    )
    (net (code "62") (name "Net-(D1-PadA)") (class "Default")
      (node (ref "D1") (pin "A") (pinfunction "A_A") (pintype "passive"))
      (node (ref "S1") (pin "4") (pinfunction "4_4") (pintype "passive"))
      (node (ref "S2") (pin "4") (pinfunction "4_4") (pintype "passive"))
      (node (ref "S3") (pin "4") (pinfunction "4_4") (pintype "passive"))
      (node (ref "S4") (pin "4") (pinfunction "4_4") (pintype "passive"))
      (node (ref "S5") (pin "4") (pinfunction "4_4") (pintype "passive"))
    )
    (net (code "63") (name "Net-(D2-PadA)") (class "Default")
      (node (ref "D2") (pin "A") (pinfunction "A_A") (pintype "passive"))
      (node (ref "S11") (pin "4") (pinfunction "4_4") (pintype "passive"))
      (node (ref "S12") (pin "4") (pinfunction "4_4") (pintype "passive"))
      (node (ref "S13") (pin "4") (pinfunction "4_4") (pintype "passive"))
      (node (ref "S14") (pin "4") (pinfunction "4_4") (pintype "passive"))
      (node (ref "S15") (pin "4") (pinfunction "4_4") (pintype "passive"))
    )
    (net (code "64") (name "Net-(D3-PadA)") (class "Default")
      (node (ref "D3") (pin "A") (pinfunction "A_A") (pintype "passive"))
      (node (ref "S21") (pin "4") (pinfunction "4_4") (pintype "passive"))
      (node (ref "S22") (pin "4") (pinfunction "4_4") (pintype "passive"))
      (node (ref "S23") (pin "4") (pinfunction "4_4") (pintype "passive"))
      (node (ref "S24") (pin "4") (pinfunction "4_4") (pintype "passive"))
      (node (ref "S25") (pin "4") (pinfunction "4_4") (pintype "passive"))
    )
    (net (code "65") (name "Net-(D4-PadA)") (class "Default")
      (node (ref "D4") (pin "A") (pinfunction "A_A") (pintype "passive"))
      (node (ref "S31") (pin "4") (pinfunction "4_4") (pintype "passive"))
      (node (ref "S32") (pin "4") (pinfunction "4_4") (pintype "passive"))
      (node (ref "S33") (pin "4") (pinfunction "4_4") (pintype "passive"))
      (node (ref "S34") (pin "4") (pinfunction "4_4") (pintype "passive"))
      (node (ref "S35") (pin "4") (pinfunction "4_4") (pintype "passive"))
    )
    (net (code "66") (name "Net-(D5-PadA)") (class "Default")
      (node (ref "D5") (pin "A") (pinfunction "A_A") (pintype "passive"))
      (node (ref "S10") (pin "4") (pinfunction "4_4") (pintype "passive"))
      (node (ref "S6") (pin "4") (pinfunction "4_4") (pintype "passive"))
      (node (ref "S7") (pin "4") (pinfunction "4_4") (pintype "passive"))
      (node (ref "S8") (pin "4") (pinfunction "4_4") (pintype "passive"))
      (node (ref "S9") (pin "4") (pinfunction "4_4") (pintype "passive"))
    )
    (net (code "67") (name "Net-(D6-PadA)") (class "Default")
      (node (ref "D6") (pin "A") (pinfunction "A_A") (pintype "passive"))
      (node (ref "S16") (pin "4") (pinfunction "4_4") (pintype "passive"))
      (node (ref "S17") (pin "4") (pinfunction "4_4") (pintype "passive"))
      (node (ref "S18") (pin "4") (pinfunction "4_4") (pintype "passive"))
      (node (ref "S19") (pin "4") (pinfunction "4_4") (pintype "passive"))
      (node (ref "S20") (pin "4") (pinfunction "4_4") (pintype "passive"))
    )
    (net (code "68") (name "Net-(D7-PadA)") (class "Default")
      (node (ref "D7") (pin "A") (pinfunction "A_A") (pintype "passive"))
      (node (ref "S26") (pin "4") (pinfunction "4_4") (pintype "passive"))
      (node (ref "S27") (pin "4") (pinfunction "4_4") (pintype "passive"))
      (node (ref "S28") (pin "4") (pinfunction "4_4") (pintype "passive"))
      (node (ref "S29") (pin "4") (pinfunction "4_4") (pintype "passive"))
      (node (ref "S30") (pin "4") (pinfunction "4_4") (pintype "passive"))
    )
    (net (code "69") (name "Net-(D8-PadA)") (class "Default")
      (node (ref "D8") (pin "A") (pinfunction "A_A") (pintype "passive"))
      (node (ref "S36") (pin "4") (pinfunction "4_4") (pintype "passive"))
      (node (ref "S37") (pin "4") (pinfunction "4_4") (pintype "passive"))
      (node (ref "S38") (pin "4") (pinfunction "4_4") (pintype "passive"))
      (node (ref "S39") (pin "4") (pinfunction "4_4") (pintype "passive"))
      (node (ref "S40") (pin "4") (pinfunction "4_4") (pintype "passive"))
    )
    (net (code "70") (name "Net-(D10-PadC)") (class "Default")
      (node (ref "D10") (pin "C") (pinfunction "C_C") (pintype "passive"))
      (node (ref "T2") (pin "B") (pinfunction "B_B") (pintype "passive"))
    )
    (net (code "71") (name "Net-(Q1-2)") (class "Default")
      (node (ref "Q1") (pin "3") (pinfunction "2_3") (pintype "passive"))
      (node (ref "ULA") (pin "39") (pinfunction "OSC_39") (pintype "output"))
    )
    (net (code "72") (name "Net-(R54-Pad1)") (class "Default")
      (node (ref "R54") (pin "1") (pinfunction "1_1") (pintype "passive"))
      (node (ref "T6") (pin "E") (pinfunction "E_E") (pintype "passive"))
    )
    (net (code "73") (name "Net-(R56-Pad1)") (class "Default")
      (node (ref "R56") (pin "1") (pinfunction "1_1") (pintype "passive"))
      (node (ref "R57") (pin "2") (pinfunction "2_2") (pintype "passive"))
      (node (ref "R58") (pin "2") (pinfunction "2_2") (pintype "passive"))
      (node (ref "T6") (pin "B") (pinfunction "B_B") (pintype "passive"))
    )
    (net (code "74") (name "Net-(SPKR-Pad1)") (class "Default")
      (node (ref "SPKR") (pin "1") (pinfunction "1_1") (pintype "passive"))
      (node (ref "T2") (pin "E") (pinfunction "E_E") (pintype "passive"))
    )
    (net (code "75") (name "Net-(T1-B)") (class "Default")
      (node (ref "C13") (pin "2") (pinfunction "2_2") (pintype "passive"))
      (node (ref "R39") (pin "1") (pinfunction "1_1") (pintype "passive"))
      (node (ref "T1") (pin "1") (pinfunction "B_1") (pintype "passive"))
    )
    (net (code "76") (name "Net-(T1-C)") (class "Default")
      (node (ref "C16") (pin "1") (pinfunction "1_1") (pintype "passive"))
      (node (ref "R47") (pin "1") (pinfunction "1_1") (pintype "passive"))
      (node (ref "T1") (pin "3") (pinfunction "C_3") (pintype "passive"))
    )
    (net (code "77") (name "Net-(T4-B)") (class "Default")
      (node (ref "C12") (pin "2") (pinfunction "2_2") (pintype "passive"))
      (node (ref "R38") (pin "1") (pinfunction "1_1") (pintype "passive"))
      (node (ref "T4") (pin "1") (pinfunction "B_1") (pintype "passive"))
    )
    (net (code "78") (name "Net-(T4-C)") (class "Default")
      (node (ref "C15") (pin "1") (pinfunction "1_1") (pintype "passive"))
      (node (ref "R48") (pin "1") (pinfunction "1_1") (pintype "passive"))
      (node (ref "T4") (pin "3") (pinfunction "C_3") (pintype "passive"))
    )
    (net (code "79") (name "Net-(U$1-Q0)") (class "Default")
      (node (ref "U$1") (pin "19") (pinfunction "Q0_19") (pintype "bidirectional"))
      (node (ref "ULA_RAM") (pin "5") (pinfunction "A9_5") (pintype "input"))
    )
    (net (code "80") (name "Net-(U$1-Q1)") (class "Default")
      (node (ref "U$1") (pin "18") (pinfunction "Q1_18") (pintype "bidirectional"))
      (node (ref "ULA_RAM") (pin "3") (pinfunction "A7_3") (pintype "input"))
    )
    (net (code "81") (name "Net-(U$1-Q2)") (class "Default")
      (node (ref "U$1") (pin "17") (pinfunction "Q2_17") (pintype "bidirectional"))
      (node (ref "ULA_RAM") (pin "2") (pinfunction "A6_2") (pintype "input"))
    )
    (net (code "82") (name "Net-(U$1-Q3)") (class "Default")
      (node (ref "U$1") (pin "16") (pinfunction "Q3_16") (pintype "bidirectional"))
      (node (ref "ULA_RAM") (pin "26") (pinfunction "A4_26") (pintype "input"))
    )
    (net (code "83") (name "Net-(U$1-Q4)") (class "Default")
      (node (ref "U$1") (pin "15") (pinfunction "Q4_15") (pintype "bidirectional"))
      (node (ref "ULA_RAM") (pin "24") (pinfunction "A2_24") (pintype "input"))
    )
    (net (code "84") (name "Net-(U$1-Q5)") (class "Default")
      (node (ref "U$1") (pin "14") (pinfunction "Q5_14") (pintype "bidirectional"))
      (node (ref "ULA_RAM") (pin "23") (pinfunction "A1_23") (pintype "input"))
    )
    (net (code "85") (name "Net-(U$1-Q6)") (class "Default")
      (node (ref "U$1") (pin "13") (pinfunction "Q6_13") (pintype "bidirectional"))
      (node (ref "ULA_RAM") (pin "21") (pinfunction "A0_21") (pintype "input"))
    )
    (net (code "86") (name "Net-(U$2-CHROMA_BIAS)") (class "Default")
      (node (ref "C14") (pin "1") (pinfunction "1_1") (pintype "passive"))
      (node (ref "R40") (pin "2") (pinfunction "2_2") (pintype "passive"))
      (node (ref "U$2") (pin "3") (pinfunction "CHROMA_BIAS_3") (pintype "bidirectional"))
    )
    (net (code "87") (name "Net-(U$2-CHROMA_LAG)") (class "Default")
      (node (ref "C19") (pin "1") (pinfunction "1_1") (pintype "passive"))
      (node (ref "R44") (pin "2") (pinfunction "2_2") (pintype "passive"))
      (node (ref "U$2") (pin "18") (pinfunction "CHROMA_LAG_18") (pintype "bidirectional"))
    )
    (net (code "88") (name "Net-(U$2-CHROMA_LEAD)") (class "Default")
      (node (ref "C17") (pin "1") (pinfunction "1_1") (pintype "passive"))
      (node (ref "U$2") (pin "1") (pinfunction "CHROMA_LEAD_1") (pintype "bidirectional"))
    )
    (net (code "89") (name "Net-(U$2-CHROMA_OSC)") (class "Default")
      (node (ref "R45") (pin "2") (pinfunction "2_2") (pintype "passive"))
      (node (ref "R46") (pin "1") (pinfunction "1_1") (pintype "passive"))
      (node (ref "U$2") (pin "17") (pinfunction "CHROMA_OSC_17") (pintype "bidirectional"))
    )
    (net (code "90") (name "Net-(U$2-CHROMA_SUB)") (class "Default")
      (node (ref "C29") (pin "+") (pinfunction "+_+") (pintype "passive"))
      (node (ref "R51") (pin "1") (pinfunction "1_1") (pintype "passive"))
      (node (ref "U$2") (pin "13") (pinfunction "CHROMA_SUB_13") (pintype "bidirectional"))
    )
    (net (code "91") (name "Net-(U$2-U_INPUT)") (class "Default")
      (node (ref "C22") (pin "1") (pinfunction "1_1") (pintype "passive"))
      (node (ref "R47") (pin "2") (pinfunction "2_2") (pintype "passive"))
      (node (ref "U$2") (pin "4") (pinfunction "U_INPUT_4") (pintype "bidirectional"))
    )
    (net (code "92") (name "Net-(U$2-VIDEO_INPUT)") (class "Default")
      (node (ref "R49") (pin "2") (pinfunction "2_2") (pintype "passive"))
      (node (ref "U$2") (pin "12") (pinfunction "VIDEO_INPUT_12") (pintype "bidirectional"))
    )
    (net (code "93") (name "Net-(U$2-V_INPUT)") (class "Default")
      (node (ref "C21") (pin "1") (pinfunction "1_1") (pintype "passive"))
      (node (ref "R48") (pin "2") (pinfunction "2_2") (pintype "passive"))
      (node (ref "U$2") (pin "2") (pinfunction "V_INPUT_2") (pintype "bidirectional"))
    )
    (net (code "94") (name "Net-(U$3-S)") (class "Default")
      (node (ref "REGS") (pin "3") (pinfunction "3_3") (pintype "passive"))
      (node (ref "REGS") (pin "4") (pinfunction "4_4") (pintype "passive"))
      (node (ref "U$3") (pin "3") (pinfunction "S_3") (pintype "passive"))
      (node (ref "VPOW") (pin "2") (pinfunction "2_2") (pintype "passive"))
    )
    (net (code "95") (name "Net-(ULA-CASL)") (class "Default")
      (node (ref "ULA") (pin "1") (pinfunction "CASL_1") (pintype "output"))
      (node (ref "ULA_RAM") (pin "20") (pinfunction "~{CE}_20") (pintype "input"))
    )
    (net (code "96") (name "Net-(ULA-CASS{slash}SPKR)") (class "Default")
      (node (ref "C10") (pin "1") (pinfunction "1_1") (pintype "passive"))
      (node (ref "C11") (pin "1") (pinfunction "1_1") (pintype "passive"))
      (node (ref "D10") (pin "A") (pinfunction "A_A") (pintype "passive"))
      (node (ref "D9") (pin "C") (pinfunction "C_C") (pintype "passive"))
      (node (ref "R34") (pin "2") (pinfunction "2_2") (pintype "passive"))
      (node (ref "R35") (pin "1") (pinfunction "1_1") (pintype "passive"))
      (node (ref "ULA") (pin "28") (pinfunction "CASS/SPKR_28") (pintype "output"))
    )
    (net (code "97") (name "Net-(ULA-D0)") (class "Default")
      (node (ref "R4") (pin "2") (pinfunction "2_2") (pintype "passive"))
      (node (ref "ULA") (pin "18") (pinfunction "D0_18") (pintype "bidirectional"))
      (node (ref "ULA_RAM") (pin "11") (pinfunction "DQ0_11") (pintype "bidirectional"))
    )
    (net (code "98") (name "Net-(ULA-D1)") (class "Default")
      (node (ref "R5") (pin "2") (pinfunction "2_2") (pintype "passive"))
      (node (ref "ULA") (pin "21") (pinfunction "D1_21") (pintype "bidirectional"))
      (node (ref "ULA_RAM") (pin "12") (pinfunction "DQ1_12") (pintype "bidirectional"))
    )
    (net (code "99") (name "Net-(ULA-D2)") (class "Default")
      (node (ref "R6") (pin "2") (pinfunction "2_2") (pintype "passive"))
      (node (ref "ULA") (pin "22") (pinfunction "D2_22") (pintype "bidirectional"))
      (node (ref "ULA_RAM") (pin "13") (pinfunction "DQ2_13") (pintype "bidirectional"))
    )
    (net (code "100") (name "Net-(ULA-D3)") (class "Default")
      (node (ref "R1") (pin "2") (pinfunction "2_2") (pintype "passive"))
      (node (ref "ULA") (pin "25") (pinfunction "D3_25") (pintype "bidirectional"))
      (node (ref "ULA_RAM") (pin "15") (pinfunction "DQ3_15") (pintype "bidirectional"))
    )
    (net (code "101") (name "Net-(ULA-D4)") (class "Default")
      (node (ref "R2") (pin "2") (pinfunction "2_2") (pintype "passive"))
      (node (ref "ULA") (pin "27") (pinfunction "D4_27") (pintype "bidirectional"))
      (node (ref "ULA_RAM") (pin "16") (pinfunction "DQ4_16") (pintype "bidirectional"))
    )
    (net (code "102") (name "Net-(ULA-D5)") (class "Default")
      (node (ref "R3") (pin "2") (pinfunction "2_2") (pintype "passive"))
      (node (ref "ULA") (pin "29") (pinfunction "D5_29") (pintype "bidirectional"))
      (node (ref "ULA_RAM") (pin "17") (pinfunction "DQ5_17") (pintype "bidirectional"))
    )
    (net (code "103") (name "Net-(ULA-D6)") (class "Default")
      (node (ref "R7") (pin "2") (pinfunction "2_2") (pintype "passive"))
      (node (ref "ULA") (pin "30") (pinfunction "D6_30") (pintype "bidirectional"))
      (node (ref "ULA_RAM") (pin "18") (pinfunction "DQ6_18") (pintype "bidirectional"))
    )
    (net (code "104") (name "Net-(ULA-D7)") (class "Default")
      (node (ref "R8") (pin "2") (pinfunction "2_2") (pintype "passive"))
      (node (ref "ULA") (pin "31") (pinfunction "D7_31") (pintype "bidirectional"))
      (node (ref "ULA_RAM") (pin "19") (pinfunction "DQ7_19") (pintype "bidirectional"))
    )
    (net (code "105") (name "Net-(ULA-DRAMWEL)") (class "Default")
      (node (ref "ULA") (pin "4") (pinfunction "DRAMWEL_4") (pintype "output"))
      (node (ref "ULA_RAM") (pin "27") (pinfunction "~{WE}_27") (pintype "input"))
    )
    (net (code "106") (name "Net-(ULA-VCC{slash}VAN)") (class "Default")
      (node (ref "C7") (pin "1") (pinfunction "1_1") (pintype "passive"))
      (node (ref "R33") (pin "1") (pinfunction "1_1") (pintype "passive"))
      (node (ref "ULA") (pin "13") (pinfunction "VCC/VAN_13") (pintype "output"))
    )
    (net (code "107") (name "Net-(Z80A-BUSRQ)") (class "Default")
      (node (ref "R62") (pin "2") (pinfunction "2_2") (pintype "passive"))
      (node (ref "Z80A") (pin "25") (pinfunction "BUSRQ_25") (pintype "input"))
    )
    (net (code "108") (name "Net-(Z80A-NMI)") (class "Default")
      (node (ref "R61") (pin "2") (pinfunction "2_2") (pintype "passive"))
      (node (ref "Z80A") (pin "17") (pinfunction "NMI_17") (pintype "input"))
    )
    (net (code "109") (name "Net-(Z80A-RESET)") (class "Default")
      (node (ref "K10") (pin "3") (pinfunction "3_3") (pintype "passive"))
      (node (ref "R59") (pin "1") (pinfunction "1_1") (pintype "passive"))
      (node (ref "Z80A") (pin "26") (pinfunction "RESET_26") (pintype "input"))
    )
    (net (code "110") (name "Net-(Z80A-WAIT)") (class "Default")
      (node (ref "R60") (pin "2") (pinfunction "2_2") (pintype "passive"))
      (node (ref "Z80A") (pin "24") (pinfunction "WAIT_24") (pintype "input"))
    )
    (net (code "111") (name "PHICPU") (class "Default")
      (node (ref "C5") (pin "1") (pinfunction "1_1") (pintype "passive"))
      (node (ref "R30") (pin "2") (pinfunction "2_2") (pintype "passive"))
      (node (ref "R32") (pin "2") (pinfunction "2_2") (pintype "passive"))
      (node (ref "ULA") (pin "32") (pinfunction "PHICPU_32") (pintype "output"))
    )
    (net (code "112") (name "RAM_CE") (class "Default")
      (node (ref "32KRAM") (pin "20") (pinfunction "~{CE}_20") (pintype "input"))
      (node (ref "IC3") (pin "2") (pinfunction "O_2") (pintype "output"))
    )
    (net (code "113") (name "RAM_OE") (class "Default")
      (node (ref "32KRAM") (pin "22") (pinfunction "~{OE}_22") (pintype "input"))
      (node (ref "IC1") (pin "3") (pinfunction "O_3") (pintype "output"))
    )
    (net (code "114") (name "RAM_WE") (class "Default")
      (node (ref "32KRAM") (pin "27") (pinfunction "~{WE}_27") (pintype "input"))
      (node (ref "IC1") (pin "6") (pinfunction "O_6") (pintype "output"))
    )
    (net (code "115") (name "RASL") (class "Default")
      (node (ref "IC3") (pin "13") (pinfunction "I_13") (pintype "input"))
      (node (ref "R25") (pin "2") (pinfunction "2_2") (pintype "passive"))
      (node (ref "ULA") (pin "35") (pinfunction "RASL_35") (pintype "output"))
    )
    (net (code "116") (name "READ") (class "Default")
      (node (ref "IC1") (pin "1") (pinfunction "I0_1") (pintype "input"))
      (node (ref "ULA") (pin "3") (pinfunction "RDL_3") (pintype "output"))
      (node (ref "Z80A") (pin "21") (pinfunction "RD_21") (pintype "output"))
    )
    (net (code "117") (name "ROM_CE") (class "Default")
      (node (ref "32K_ROM") (pin "23") (pinfunction "~{CE}_23") (pintype "input"))
    )
    (net (code "118") (name "ROM_CS") (class "Default")
      (node (ref "R63") (pin "1") (pinfunction "1_1") (pintype "passive"))
      (node (ref "ULA") (pin "34") (pinfunction "ROMCSL_34") (pintype "output"))
    )
    (net (code "119") (name "URAMA0") (class "Default")
      (node (ref "R20") (pin "2") (pinfunction "2_2") (pintype "passive"))
      (node (ref "U$1") (pin "6") (pinfunction "D4_6") (pintype "bidirectional"))
      (node (ref "ULA") (pin "5") (pinfunction "DMA0_5") (pintype "output"))
      (node (ref "ULA_RAM") (pin "8") (pinfunction "A12_8") (pintype "input"))
    )
    (net (code "120") (name "URAMA1") (class "Default")
      (node (ref "R19") (pin "2") (pinfunction "2_2") (pintype "passive"))
      (node (ref "U$1") (pin "3") (pinfunction "D1_3") (pintype "bidirectional"))
      (node (ref "ULA") (pin "6") (pinfunction "DMA1_6") (pintype "output"))
      (node (ref "ULA_RAM") (pin "4") (pinfunction "A8_4") (pintype "input"))
    )
    (net (code "121") (name "URAMA2") (class "Default")
      (node (ref "R18") (pin "2") (pinfunction "2_2") (pintype "passive"))
      (node (ref "U$1") (pin "8") (pinfunction "D6_8") (pintype "bidirectional"))
      (node (ref "ULA") (pin "7") (pinfunction "DMA2_7") (pintype "output"))
      (node (ref "ULA_RAM") (pin "25") (pinfunction "A3_25") (pintype "input"))
    )
    (net (code "122") (name "URAMA3") (class "Default")
      (node (ref "R17") (pin "2") (pinfunction "2_2") (pintype "passive"))
      (node (ref "U$1") (pin "5") (pinfunction "D3_5") (pintype "bidirectional"))
      (node (ref "ULA") (pin "8") (pinfunction "DMA3_8") (pintype "input"))
      (node (ref "ULA_RAM") (pin "6") (pinfunction "A10_6") (pintype "input"))
    )
    (net (code "123") (name "URAMA4") (class "Default")
      (node (ref "R24") (pin "1") (pinfunction "1_1") (pintype "passive"))
      (node (ref "U$1") (pin "4") (pinfunction "D2_4") (pintype "bidirectional"))
      (node (ref "ULA") (pin "9") (pinfunction "DMA4_9") (pintype "input"))
      (node (ref "ULA_RAM") (pin "7") (pinfunction "A11_7") (pintype "input"))
    )
    (net (code "124") (name "URAMA5") (class "Default")
      (node (ref "R23") (pin "1") (pinfunction "1_1") (pintype "passive"))
      (node (ref "U$1") (pin "2") (pinfunction "D0_2") (pintype "bidirectional"))
      (node (ref "ULA") (pin "10") (pinfunction "DMA5_10") (pintype "input"))
      (node (ref "ULA_RAM") (pin "9") (pinfunction "A13_9") (pintype "input"))
    )
    (net (code "125") (name "URAMA6") (class "Default")
      (node (ref "R22") (pin "1") (pinfunction "1_1") (pintype "passive"))
      (node (ref "U$1") (pin "7") (pinfunction "D5_7") (pintype "bidirectional"))
      (node (ref "ULA") (pin "11") (pinfunction "DMA6_11") (pintype "input"))
      (node (ref "ULA_RAM") (pin "1") (pinfunction "A5_1") (pintype "input"))
    )
    (net (code "126") (name "VCC") (class "Default")
      (node (ref "157") (pin "16") (pinfunction "VCC_16") (pintype "bidirectional"))
      (node (ref "157-1") (pin "16") (pinfunction "VCC_16") (pintype "bidirectional"))
      (node (ref "32KRAM") (pin "28") (pinfunction "VCC_28") (pintype "power_in"))
      (node (ref "32K_ROM") (pin "2") (pinfunction "VPP_2") (pintype "input"))
      (node (ref "32K_ROM") (pin "32") (pinfunction "VCC_32") (pintype "power_in"))
      (node (ref "C1") (pin "1") (pinfunction "1_1") (pintype "passive"))
      (node (ref "C2") (pin "1") (pinfunction "1_1") (pintype "passive"))
      (node (ref "C3") (pin "1") (pinfunction "1_1") (pintype "passive"))
      (node (ref "C30") (pin "+") (pinfunction "+_+") (pintype "passive"))
      (node (ref "C4") (pin "1") (pinfunction "1_1") (pintype "passive"))
      (node (ref "C6") (pin "1") (pinfunction "1_1") (pintype "passive"))
      (node (ref "C8") (pin "1") (pinfunction "1_1") (pintype "passive"))
      (node (ref "IC1") (pin "14") (pinfunction "VCC_14") (pintype "power_in"))
      (node (ref "IC3") (pin "14") (pinfunction "VCC_14") (pintype "power_in"))
      (node (ref "R10") (pin "2") (pinfunction "2_2") (pintype "passive"))
      (node (ref "R11") (pin "2") (pinfunction "2_2") (pintype "passive"))
      (node (ref "R12") (pin "2") (pinfunction "2_2") (pintype "passive"))
      (node (ref "R13") (pin "2") (pinfunction "2_2") (pintype "passive"))
      (node (ref "R14") (pin "2") (pinfunction "2_2") (pintype "passive"))
      (node (ref "R15") (pin "2") (pinfunction "2_2") (pintype "passive"))
      (node (ref "R16") (pin "2") (pinfunction "2_2") (pintype "passive"))
      (node (ref "R21") (pin "2") (pinfunction "2_2") (pintype "passive"))
      (node (ref "R26") (pin "2") (pinfunction "2_2") (pintype "passive"))
      (node (ref "R27") (pin "2") (pinfunction "2_2") (pintype "passive"))
      (node (ref "R28") (pin "2") (pinfunction "2_2") (pintype "passive"))
      (node (ref "R29") (pin "2") (pinfunction "2_2") (pintype "passive"))
      (node (ref "R31") (pin "1") (pinfunction "1_1") (pintype "passive"))
      (node (ref "R32") (pin "1") (pinfunction "1_1") (pintype "passive"))
      (node (ref "R33") (pin "2") (pinfunction "2_2") (pintype "passive"))
      (node (ref "R34") (pin "1") (pinfunction "1_1") (pintype "passive"))
      (node (ref "R38") (pin "2") (pinfunction "2_2") (pintype "passive"))
      (node (ref "R39") (pin "2") (pinfunction "2_2") (pintype "passive"))
      (node (ref "R40") (pin "1") (pinfunction "1_1") (pintype "passive"))
      (node (ref "R52") (pin "2") (pinfunction "2_2") (pintype "passive"))
      (node (ref "R59") (pin "2") (pinfunction "2_2") (pintype "passive"))
      (node (ref "R60") (pin "1") (pinfunction "1_1") (pintype "passive"))
      (node (ref "R61") (pin "1") (pinfunction "1_1") (pintype "passive"))
      (node (ref "R62") (pin "1") (pinfunction "1_1") (pintype "passive"))
      (node (ref "R9") (pin "2") (pinfunction "2_2") (pintype "passive"))
      (node (ref "REGS") (pin "1") (pinfunction "1_1") (pintype "passive"))
      (node (ref "ROMS") (pin "3") (pinfunction "3_3") (pintype "passive"))
      (node (ref "T1") (pin "2") (pinfunction "E_2") (pintype "passive"))
      (node (ref "T2") (pin "C") (pinfunction "C_C") (pintype "passive"))
      (node (ref "T4") (pin "2") (pinfunction "E_2") (pintype "passive"))
      (node (ref "T7") (pin "C") (pinfunction "C_C") (pintype "passive"))
      (node (ref "U$1") (pin "20") (pinfunction "VCC_20") (pintype "bidirectional"))
      (node (ref "ULA") (pin "14") (pinfunction "VCC_14") (pintype "output"))
      (node (ref "ULA_RAM") (pin "28") (pinfunction "VCC_28") (pintype "power_in"))
      (node (ref "Z80A") (pin "11") (pinfunction "VCC_11") (pintype "power_in"))
    )
    (net (code "127") (name "VIDEO") (class "Default")
      (node (ref "R55") (pin "1") (pinfunction "1_1") (pintype "passive"))
      (node (ref "T5") (pin "E") (pinfunction "E_E") (pintype "passive"))
      (node (ref "VID") (pin "1") (pinfunction "1_1") (pintype "passive"))
    )
    (net (code "128") (name "VID_U") (class "Default")
      (node (ref "C16") (pin "2") (pinfunction "2_2") (pintype "passive"))
      (node (ref "R42") (pin "1") (pinfunction "1_1") (pintype "passive"))
      (node (ref "ULA") (pin "15") (pinfunction "U_15") (pintype "output"))
    )
    (net (code "129") (name "VID_V") (class "Default")
      (node (ref "C15") (pin "2") (pinfunction "2_2") (pintype "passive"))
      (node (ref "R41") (pin "1") (pinfunction "1_1") (pintype "passive"))
      (node (ref "ULA") (pin "16") (pinfunction "V_16") (pintype "output"))
    )
    (net (code "130") (name "VID_YL") (class "Default")
      (node (ref "C12") (pin "1") (pinfunction "1_1") (pintype "passive"))
      (node (ref "C13") (pin "1") (pinfunction "1_1") (pintype "passive"))
      (node (ref "R50") (pin "2") (pinfunction "2_2") (pintype "passive"))
      (node (ref "R57") (pin "1") (pinfunction "1_1") (pintype "passive"))
      (node (ref "ULA") (pin "17") (pinfunction "YL_17") (pintype "output"))
    )
    (net (code "131") (name "WRITE") (class "Default")
      (node (ref "IC1") (pin "5") (pinfunction "I1_5") (pintype "input"))
      (node (ref "ULA") (pin "2") (pinfunction "WRL_2") (pintype "output"))
      (node (ref "Z80A") (pin "22") (pinfunction "WR_22") (pintype "output"))
    )
    (net (code "132") (name "unconnected-(157-1-3A-Pad11)") (class "Default")
      (node (ref "157-1") (pin "11") (pinfunction "3A_11") (pintype "bidirectional"))
    )
    (net (code "133") (name "unconnected-(157-1-3B-Pad10)") (class "Default")
      (node (ref "157-1") (pin "10") (pinfunction "3B_10") (pintype "bidirectional"))
    )
    (net (code "134") (name "unconnected-(157-1-3Y-Pad9)") (class "Default")
      (node (ref "157-1") (pin "9") (pinfunction "3Y_9") (pintype "bidirectional"))
    )
    (net (code "135") (name "unconnected-(IC1C-I0-Pad9)") (class "Default")
      (node (ref "IC1") (pin "9") (pinfunction "I0_9") (pintype "input"))
    )
    (net (code "136") (name "unconnected-(IC1C-I1-Pad10)") (class "Default")
      (node (ref "IC1") (pin "10") (pinfunction "I1_10") (pintype "input"))
    )
    (net (code "137") (name "unconnected-(IC1C-O-Pad8)") (class "Default")
      (node (ref "IC1") (pin "8") (pinfunction "O_8") (pintype "output"))
    )
    (net (code "138") (name "unconnected-(IC1D-I0-Pad12)") (class "Default")
      (node (ref "IC1") (pin "12") (pinfunction "I0_12") (pintype "input"))
    )
    (net (code "139") (name "unconnected-(IC1D-I1-Pad13)") (class "Default")
      (node (ref "IC1") (pin "13") (pinfunction "I1_13") (pintype "input"))
    )
    (net (code "140") (name "unconnected-(IC1D-O-Pad11)") (class "Default")
      (node (ref "IC1") (pin "11") (pinfunction "O_11") (pintype "output"))
    )
    (net (code "141") (name "unconnected-(IC3B-I-Pad3)") (class "Default")
      (node (ref "IC3") (pin "3") (pinfunction "I_3") (pintype "input"))
    )
    (net (code "142") (name "unconnected-(IC3B-O-Pad4)") (class "Default")
      (node (ref "IC3") (pin "4") (pinfunction "O_4") (pintype "output"))
    )
    (net (code "143") (name "unconnected-(IC3C-I-Pad5)") (class "Default")
      (node (ref "IC3") (pin "5") (pinfunction "I_5") (pintype "input"))
    )
    (net (code "144") (name "unconnected-(IC3C-O-Pad6)") (class "Default")
      (node (ref "IC3") (pin "6") (pinfunction "O_6") (pintype "output"))
    )
    (net (code "145") (name "unconnected-(IC3D-I-Pad9)") (class "Default")
      (node (ref "IC3") (pin "9") (pinfunction "I_9") (pintype "input"))
    )
    (net (code "146") (name "unconnected-(IC3D-O-Pad8)") (class "Default")
      (node (ref "IC3") (pin "8") (pinfunction "O_8") (pintype "output"))
    )
    (net (code "147") (name "unconnected-(IC3E-I-Pad11)") (class "Default")
      (node (ref "IC3") (pin "11") (pinfunction "I_11") (pintype "input"))
    )
    (net (code "148") (name "unconnected-(IC3E-O-Pad10)") (class "Default")
      (node (ref "IC3") (pin "10") (pinfunction "O_10") (pintype "output"))
    )
    (net (code "149") (name "unconnected-(K10-Pad2)") (class "Default")
      (node (ref "K10") (pin "2") (pinfunction "2_2") (pintype "passive"))
    )
    (net (code "150") (name "unconnected-(K10-Pad4)") (class "Default")
      (node (ref "K10") (pin "4") (pinfunction "4_4") (pintype "passive"))
    )
    (net (code "151") (name "unconnected-(S1-Pad2)") (class "Default")
      (node (ref "S1") (pin "2") (pinfunction "2_2") (pintype "passive"))
    )
    (net (code "152") (name "unconnected-(S1-Pad3)") (class "Default")
      (node (ref "S1") (pin "3") (pinfunction "3_3") (pintype "passive"))
    )
    (net (code "153") (name "unconnected-(S2-Pad2)") (class "Default")
      (node (ref "S2") (pin "2") (pinfunction "2_2") (pintype "passive"))
    )
    (net (code "154") (name "unconnected-(S2-Pad3)") (class "Default")
      (node (ref "S2") (pin "3") (pinfunction "3_3") (pintype "passive"))
    )
    (net (code "155") (name "unconnected-(S3-Pad2)") (class "Default")
      (node (ref "S3") (pin "2") (pinfunction "2_2") (pintype "passive"))
    )
    (net (code "156") (name "unconnected-(S3-Pad3)") (class "Default")
      (node (ref "S3") (pin "3") (pinfunction "3_3") (pintype "passive"))
    )
    (net (code "157") (name "unconnected-(S4-Pad2)") (class "Default")
      (node (ref "S4") (pin "2") (pinfunction "2_2") (pintype "passive"))
    )
    (net (code "158") (name "unconnected-(S4-Pad3)") (class "Default")
      (node (ref "S4") (pin "3") (pinfunction "3_3") (pintype "passive"))
    )
    (net (code "159") (name "unconnected-(S5-Pad2)") (class "Default")
      (node (ref "S5") (pin "2") (pinfunction "2_2") (pintype "passive"))
    )
    (net (code "160") (name "unconnected-(S5-Pad3)") (class "Default")
      (node (ref "S5") (pin "3") (pinfunction "3_3") (pintype "passive"))
    )
    (net (code "161") (name "unconnected-(S6-Pad2)") (class "Default")
      (node (ref "S6") (pin "2") (pinfunction "2_2") (pintype "passive"))
    )
    (net (code "162") (name "unconnected-(S6-Pad3)") (class "Default")
      (node (ref "S6") (pin "3") (pinfunction "3_3") (pintype "passive"))
    )
    (net (code "163") (name "unconnected-(S7-Pad2)") (class "Default")
      (node (ref "S7") (pin "2") (pinfunction "2_2") (pintype "passive"))
    )
    (net (code "164") (name "unconnected-(S7-Pad3)") (class "Default")
      (node (ref "S7") (pin "3") (pinfunction "3_3") (pintype "passive"))
    )
    (net (code "165") (name "unconnected-(S8-Pad2)") (class "Default")
      (node (ref "S8") (pin "2") (pinfunction "2_2") (pintype "passive"))
    )
    (net (code "166") (name "unconnected-(S8-Pad3)") (class "Default")
      (node (ref "S8") (pin "3") (pinfunction "3_3") (pintype "passive"))
    )
    (net (code "167") (name "unconnected-(S9-Pad2)") (class "Default")
      (node (ref "S9") (pin "2") (pinfunction "2_2") (pintype "passive"))
    )
    (net (code "168") (name "unconnected-(S9-Pad3)") (class "Default")
      (node (ref "S9") (pin "3") (pinfunction "3_3") (pintype "passive"))
    )
    (net (code "169") (name "unconnected-(S10-Pad2)") (class "Default")
      (node (ref "S10") (pin "2") (pinfunction "2_2") (pintype "passive"))
    )
    (net (code "170") (name "unconnected-(S10-Pad3)") (class "Default")
      (node (ref "S10") (pin "3") (pinfunction "3_3") (pintype "passive"))
    )
    (net (code "171") (name "unconnected-(S11-Pad2)") (class "Default")
      (node (ref "S11") (pin "2") (pinfunction "2_2") (pintype "passive"))
    )
    (net (code "172") (name "unconnected-(S11-Pad3)") (class "Default")
      (node (ref "S11") (pin "3") (pinfunction "3_3") (pintype "passive"))
    )
    (net (code "173") (name "unconnected-(S12-Pad2)") (class "Default")
      (node (ref "S12") (pin "2") (pinfunction "2_2") (pintype "passive"))
    )
    (net (code "174") (name "unconnected-(S12-Pad3)") (class "Default")
      (node (ref "S12") (pin "3") (pinfunction "3_3") (pintype "passive"))
    )
    (net (code "175") (name "unconnected-(S13-Pad2)") (class "Default")
      (node (ref "S13") (pin "2") (pinfunction "2_2") (pintype "passive"))
    )
    (net (code "176") (name "unconnected-(S13-Pad3)") (class "Default")
      (node (ref "S13") (pin "3") (pinfunction "3_3") (pintype "passive"))
    )
    (net (code "177") (name "unconnected-(S14-Pad2)") (class "Default")
      (node (ref "S14") (pin "2") (pinfunction "2_2") (pintype "passive"))
    )
    (net (code "178") (name "unconnected-(S14-Pad3)") (class "Default")
      (node (ref "S14") (pin "3") (pinfunction "3_3") (pintype "passive"))
    )
    (net (code "179") (name "unconnected-(S15-Pad2)") (class "Default")
      (node (ref "S15") (pin "2") (pinfunction "2_2") (pintype "passive"))
    )
    (net (code "180") (name "unconnected-(S15-Pad3)") (class "Default")
      (node (ref "S15") (pin "3") (pinfunction "3_3") (pintype "passive"))
    )
    (net (code "181") (name "unconnected-(S16-Pad2)") (class "Default")
      (node (ref "S16") (pin "2") (pinfunction "2_2") (pintype "passive"))
    )
    (net (code "182") (name "unconnected-(S16-Pad3)") (class "Default")
      (node (ref "S16") (pin "3") (pinfunction "3_3") (pintype "passive"))
    )
    (net (code "183") (name "unconnected-(S17-Pad2)") (class "Default")
      (node (ref "S17") (pin "2") (pinfunction "2_2") (pintype "passive"))
    )
    (net (code "184") (name "unconnected-(S17-Pad3)") (class "Default")
      (node (ref "S17") (pin "3") (pinfunction "3_3") (pintype "passive"))
    )
    (net (code "185") (name "unconnected-(S18-Pad2)") (class "Default")
      (node (ref "S18") (pin "2") (pinfunction "2_2") (pintype "passive"))
    )
    (net (code "186") (name "unconnected-(S18-Pad3)") (class "Default")
      (node (ref "S18") (pin "3") (pinfunction "3_3") (pintype "passive"))
    )
    (net (code "187") (name "unconnected-(S19-Pad2)") (class "Default")
      (node (ref "S19") (pin "2") (pinfunction "2_2") (pintype "passive"))
    )
    (net (code "188") (name "unconnected-(S19-Pad3)") (class "Default")
      (node (ref "S19") (pin "3") (pinfunction "3_3") (pintype "passive"))
    )
    (net (code "189") (name "unconnected-(S20-Pad2)") (class "Default")
      (node (ref "S20") (pin "2") (pinfunction "2_2") (pintype "passive"))
    )
    (net (code "190") (name "unconnected-(S20-Pad3)") (class "Default")
      (node (ref "S20") (pin "3") (pinfunction "3_3") (pintype "passive"))
    )
    (net (code "191") (name "unconnected-(S21-Pad2)") (class "Default")
      (node (ref "S21") (pin "2") (pinfunction "2_2") (pintype "passive"))
    )
    (net (code "192") (name "unconnected-(S21-Pad3)") (class "Default")
      (node (ref "S21") (pin "3") (pinfunction "3_3") (pintype "passive"))
    )
    (net (code "193") (name "unconnected-(S22-Pad2)") (class "Default")
      (node (ref "S22") (pin "2") (pinfunction "2_2") (pintype "passive"))
    )
    (net (code "194") (name "unconnected-(S22-Pad3)") (class "Default")
      (node (ref "S22") (pin "3") (pinfunction "3_3") (pintype "passive"))
    )
    (net (code "195") (name "unconnected-(S23-Pad2)") (class "Default")
      (node (ref "S23") (pin "2") (pinfunction "2_2") (pintype "passive"))
    )
    (net (code "196") (name "unconnected-(S23-Pad3)") (class "Default")
      (node (ref "S23") (pin "3") (pinfunction "3_3") (pintype "passive"))
    )
    (net (code "197") (name "unconnected-(S24-Pad2)") (class "Default")
      (node (ref "S24") (pin "2") (pinfunction "2_2") (pintype "passive"))
    )
    (net (code "198") (name "unconnected-(S24-Pad3)") (class "Default")
      (node (ref "S24") (pin "3") (pinfunction "3_3") (pintype "passive"))
    )
    (net (code "199") (name "unconnected-(S25-Pad2)") (class "Default")
      (node (ref "S25") (pin "2") (pinfunction "2_2") (pintype "passive"))
    )
    (net (code "200") (name "unconnected-(S25-Pad3)") (class "Default")
      (node (ref "S25") (pin "3") (pinfunction "3_3") (pintype "passive"))
    )
    (net (code "201") (name "unconnected-(S26-Pad2)") (class "Default")
      (node (ref "S26") (pin "2") (pinfunction "2_2") (pintype "passive"))
    )
    (net (code "202") (name "unconnected-(S26-Pad3)") (class "Default")
      (node (ref "S26") (pin "3") (pinfunction "3_3") (pintype "passive"))
    )
    (net (code "203") (name "unconnected-(S27-Pad2)") (class "Default")
      (node (ref "S27") (pin "2") (pinfunction "2_2") (pintype "passive"))
    )
    (net (code "204") (name "unconnected-(S27-Pad3)") (class "Default")
      (node (ref "S27") (pin "3") (pinfunction "3_3") (pintype "passive"))
    )
    (net (code "205") (name "unconnected-(S28-Pad2)") (class "Default")
      (node (ref "S28") (pin "2") (pinfunction "2_2") (pintype "passive"))
    )
    (net (code "206") (name "unconnected-(S28-Pad3)") (class "Default")
      (node (ref "S28") (pin "3") (pinfunction "3_3") (pintype "passive"))
    )
    (net (code "207") (name "unconnected-(S29-Pad2)") (class "Default")
      (node (ref "S29") (pin "2") (pinfunction "2_2") (pintype "passive"))
    )
    (net (code "208") (name "unconnected-(S29-Pad3)") (class "Default")
      (node (ref "S29") (pin "3") (pinfunction "3_3") (pintype "passive"))
    )
    (net (code "209") (name "unconnected-(S30-Pad2)") (class "Default")
      (node (ref "S30") (pin "2") (pinfunction "2_2") (pintype "passive"))
    )
    (net (code "210") (name "unconnected-(S30-Pad3)") (class "Default")
      (node (ref "S30") (pin "3") (pinfunction "3_3") (pintype "passive"))
    )
    (net (code "211") (name "unconnected-(S31-Pad2)") (class "Default")
      (node (ref "S31") (pin "2") (pinfunction "2_2") (pintype "passive"))
    )
    (net (code "212") (name "unconnected-(S31-Pad3)") (class "Default")
      (node (ref "S31") (pin "3") (pinfunction "3_3") (pintype "passive"))
    )
    (net (code "213") (name "unconnected-(S32-Pad2)") (class "Default")
      (node (ref "S32") (pin "2") (pinfunction "2_2") (pintype "passive"))
    )
    (net (code "214") (name "unconnected-(S32-Pad3)") (class "Default")
      (node (ref "S32") (pin "3") (pinfunction "3_3") (pintype "passive"))
    )
    (net (code "215") (name "unconnected-(S33-Pad2)") (class "Default")
      (node (ref "S33") (pin "2") (pinfunction "2_2") (pintype "passive"))
    )
    (net (code "216") (name "unconnected-(S33-Pad3)") (class "Default")
      (node (ref "S33") (pin "3") (pinfunction "3_3") (pintype "passive"))
    )
    (net (code "217") (name "unconnected-(S34-Pad2)") (class "Default")
      (node (ref "S34") (pin "2") (pinfunction "2_2") (pintype "passive"))
    )
    (net (code "218") (name "unconnected-(S34-Pad3)") (class "Default")
      (node (ref "S34") (pin "3") (pinfunction "3_3") (pintype "passive"))
    )
    (net (code "219") (name "unconnected-(S35-Pad2)") (class "Default")
      (node (ref "S35") (pin "2") (pinfunction "2_2") (pintype "passive"))
    )
    (net (code "220") (name "unconnected-(S35-Pad3)") (class "Default")
      (node (ref "S35") (pin "3") (pinfunction "3_3") (pintype "passive"))
    )
    (net (code "221") (name "unconnected-(S36-Pad2)") (class "Default")
      (node (ref "S36") (pin "2") (pinfunction "2_2") (pintype "passive"))
    )
    (net (code "222") (name "unconnected-(S36-Pad3)") (class "Default")
      (node (ref "S36") (pin "3") (pinfunction "3_3") (pintype "passive"))
    )
    (net (code "223") (name "unconnected-(S37-Pad2)") (class "Default")
      (node (ref "S37") (pin "2") (pinfunction "2_2") (pintype "passive"))
    )
    (net (code "224") (name "unconnected-(S37-Pad3)") (class "Default")
      (node (ref "S37") (pin "3") (pinfunction "3_3") (pintype "passive"))
    )
    (net (code "225") (name "unconnected-(S38-Pad2)") (class "Default")
      (node (ref "S38") (pin "2") (pinfunction "2_2") (pintype "passive"))
    )
    (net (code "226") (name "unconnected-(S38-Pad3)") (class "Default")
      (node (ref "S38") (pin "3") (pinfunction "3_3") (pintype "passive"))
    )
    (net (code "227") (name "unconnected-(S39-Pad2)") (class "Default")
      (node (ref "S39") (pin "2") (pinfunction "2_2") (pintype "passive"))
    )
    (net (code "228") (name "unconnected-(S39-Pad3)") (class "Default")
      (node (ref "S39") (pin "3") (pinfunction "3_3") (pintype "passive"))
    )
    (net (code "229") (name "unconnected-(S40-Pad2)") (class "Default")
      (node (ref "S40") (pin "2") (pinfunction "2_2") (pintype "passive"))
    )
    (net (code "230") (name "unconnected-(S40-Pad3)") (class "Default")
      (node (ref "S40") (pin "3") (pinfunction "3_3") (pintype "passive"))
    )
    (net (code "231") (name "unconnected-(U$1-D7-Pad9)") (class "Default")
      (node (ref "U$1") (pin "9") (pinfunction "D7_9") (pintype "bidirectional"))
    )
    (net (code "232") (name "unconnected-(U$1-Q7-Pad12)") (class "Default")
      (node (ref "U$1") (pin "12") (pinfunction "Q7_12") (pintype "bidirectional"))
    )
    (net (code "233") (name "unconnected-(U$2-CHA_OUTPUT-Pad11)") (class "Default")
      (node (ref "U$2") (pin "11") (pinfunction "CHA_OUTPUT_11") (pintype "bidirectional"))
    )
    (net (code "234") (name "unconnected-(U$2-CHA_TANK0-Pad8)") (class "Default")
      (node (ref "U$2") (pin "8") (pinfunction "CHA_TANK0_8") (pintype "bidirectional"))
    )
    (net (code "235") (name "unconnected-(U$2-CHA_TANK1-Pad9)") (class "Default")
      (node (ref "U$2") (pin "9") (pinfunction "CHA_TANK1_9") (pintype "bidirectional"))
    )
    (net (code "236") (name "unconnected-(U$2-CHB_OUTPUT-Pad10)") (class "Default")
      (node (ref "U$2") (pin "10") (pinfunction "CHB_OUTPUT_10") (pintype "bidirectional"))
    )
    (net (code "237") (name "unconnected-(U$2-CHB_TANK0-Pad6)") (class "Default")
      (node (ref "U$2") (pin "6") (pinfunction "CHB_TANK0_6") (pintype "bidirectional"))
    )
    (net (code "238") (name "unconnected-(U$2-CHB_TANK1-Pad7)") (class "Default")
      (node (ref "U$2") (pin "7") (pinfunction "CHB_TANK1_7") (pintype "bidirectional"))
    )
    (net (code "239") (name "unconnected-(U$3-O-Pad1)") (class "Default")
      (node (ref "U$3") (pin "1") (pinfunction "O_1") (pintype "passive"))
    )
    (net (code "240") (name "unconnected-(U$3-P-Pad2)") (class "Default")
      (node (ref "U$3") (pin "2") (pinfunction "P_2") (pintype "passive"))
    )
    (net (code "241") (name "unconnected-(Z80A-BUSAK-Pad23)") (class "Default")
      (node (ref "Z80A") (pin "23") (pinfunction "BUSAK_23") (pintype "output"))
    )
    (net (code "242") (name "unconnected-(Z80A-HALT-Pad18)") (class "Default")
      (node (ref "Z80A") (pin "18") (pinfunction "HALT_18") (pintype "output"))
    )
    (net (code "243") (name "unconnected-(Z80A-M1-Pad27)") (class "Default")
      (node (ref "Z80A") (pin "27") (pinfunction "M1_27") (pintype "output"))
    )
    (net (code "244") (name "unconnected-(Z80A-RFSH-Pad28)") (class "Default")
      (node (ref "Z80A") (pin "28") (pinfunction "RFSH_28") (pintype "output"))
    )
  )
)
